# canSlaveV02_16s.net
KiCad netlist of a schematic drawn in EAGLE
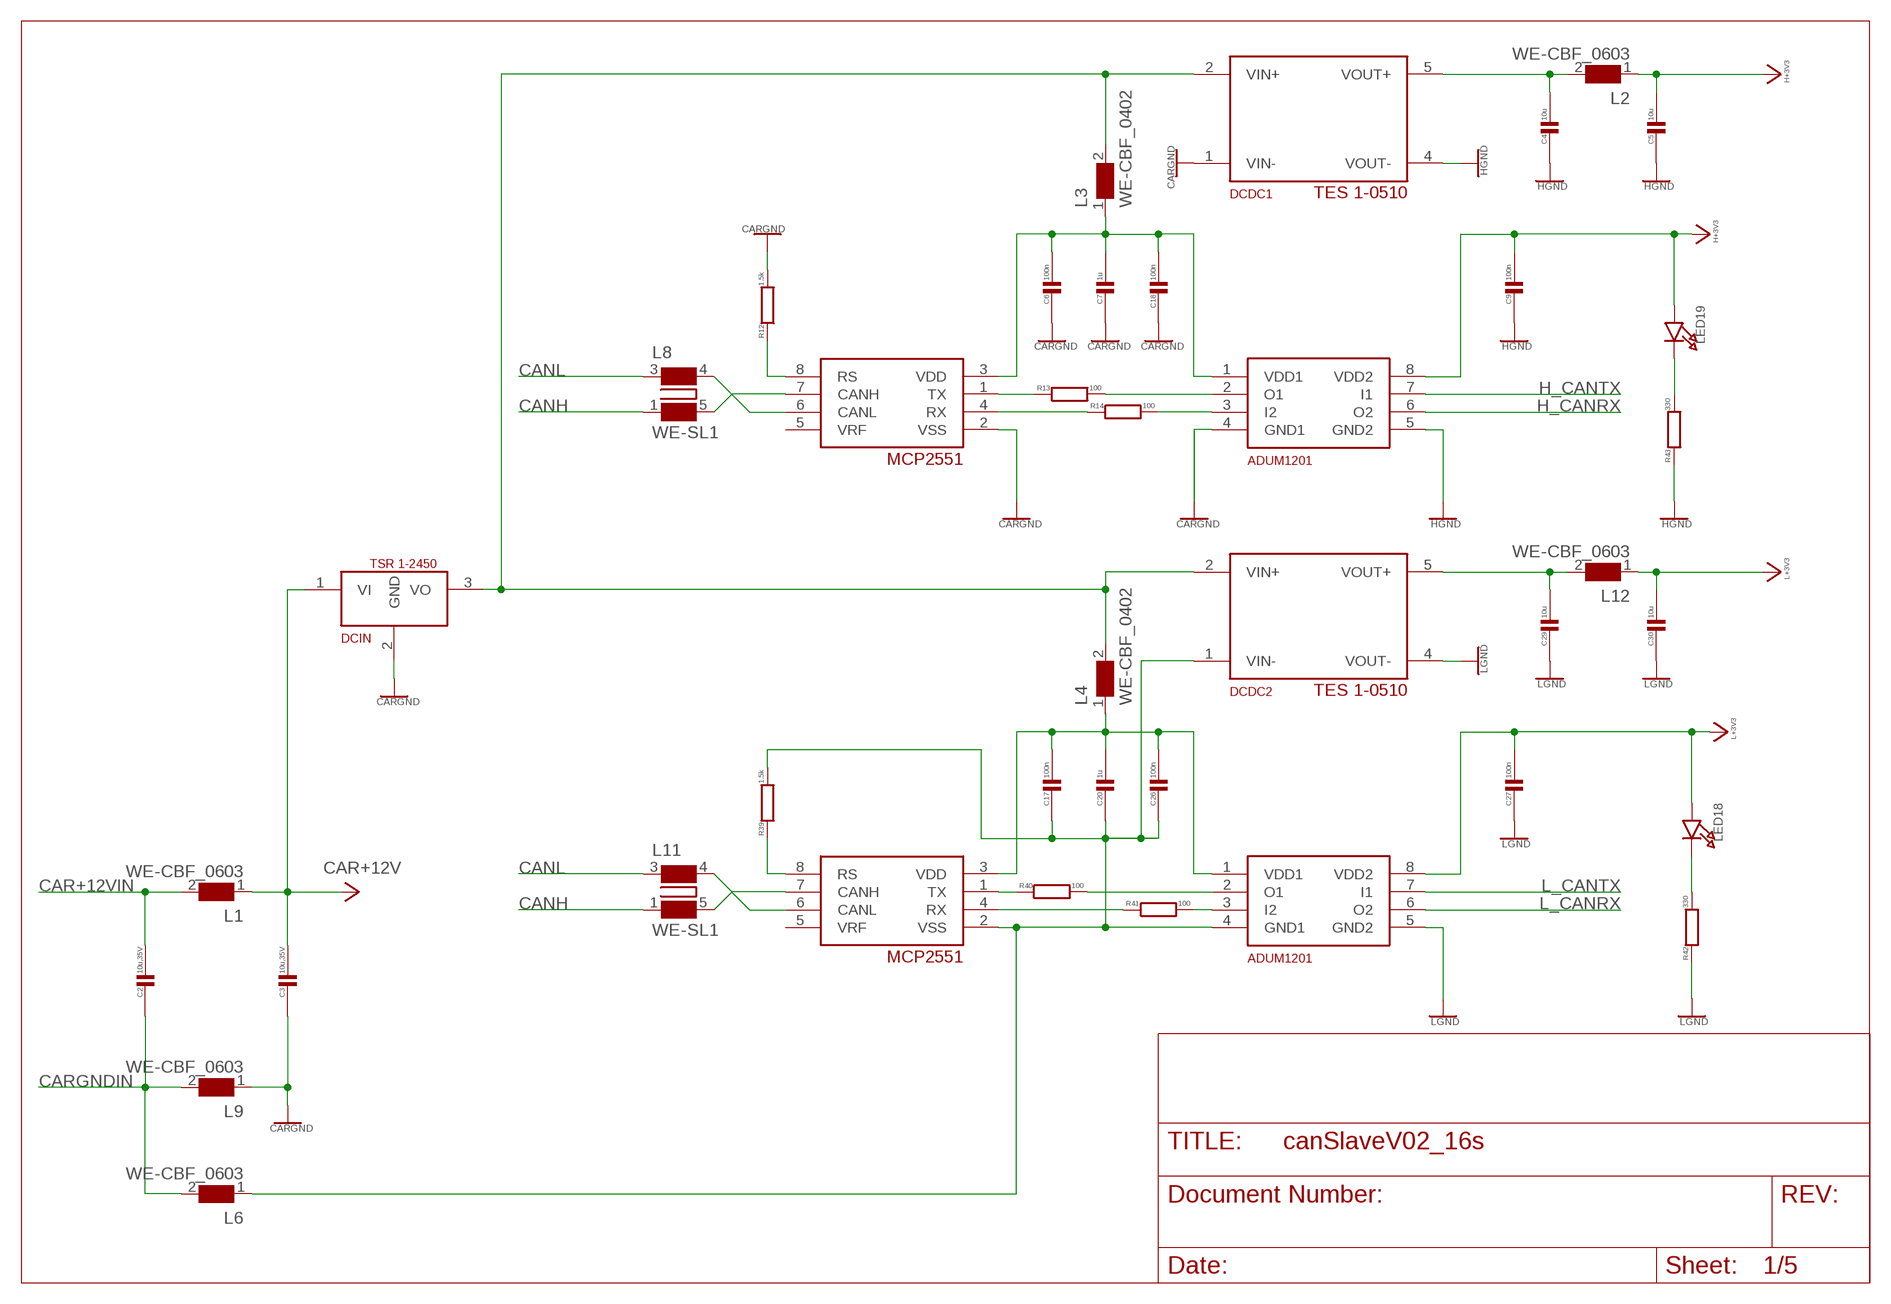
[diagram p0: schematic, sheet 1]
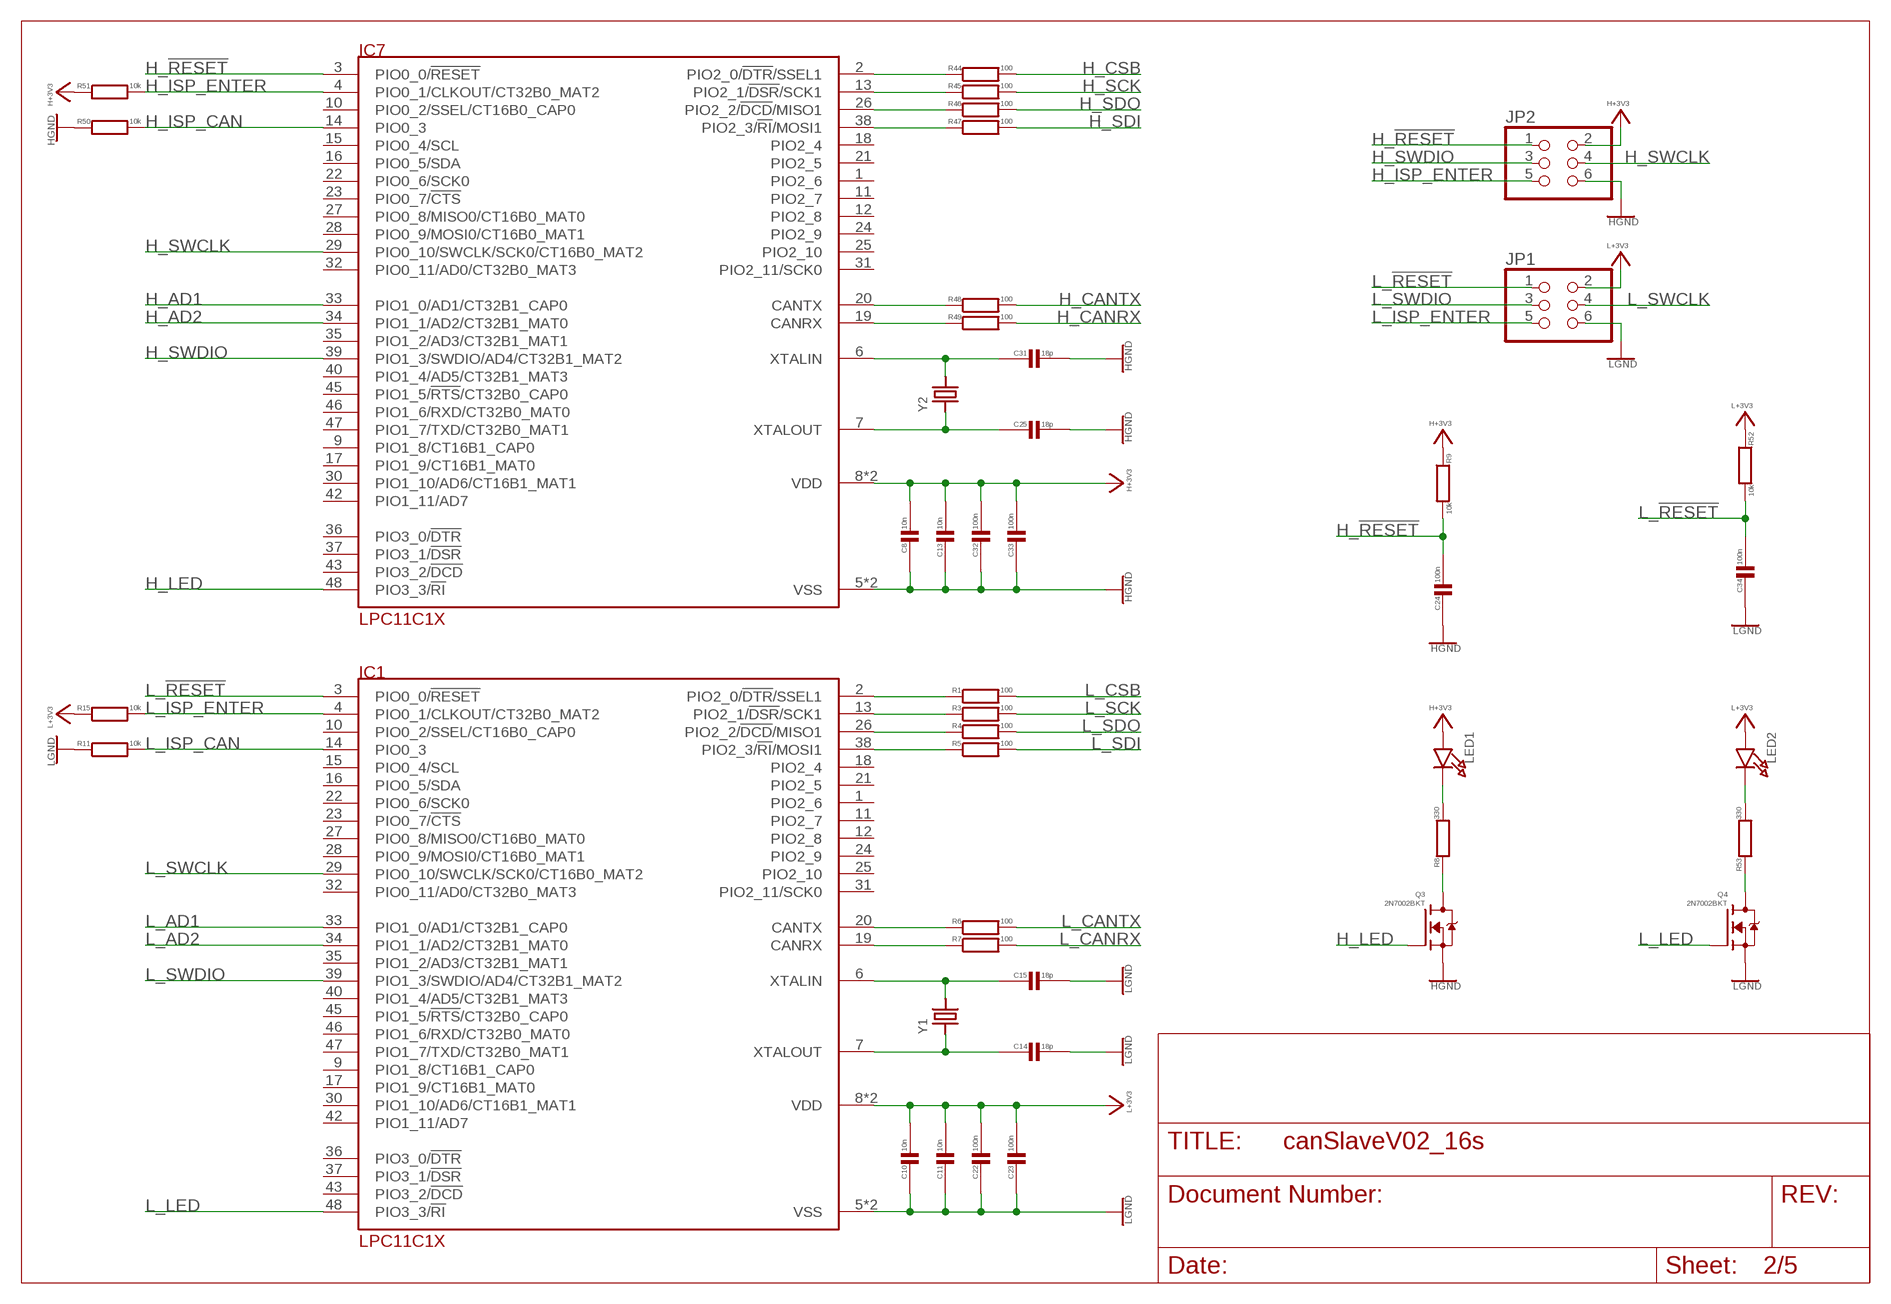
[diagram p1: schematic, sheet 2]
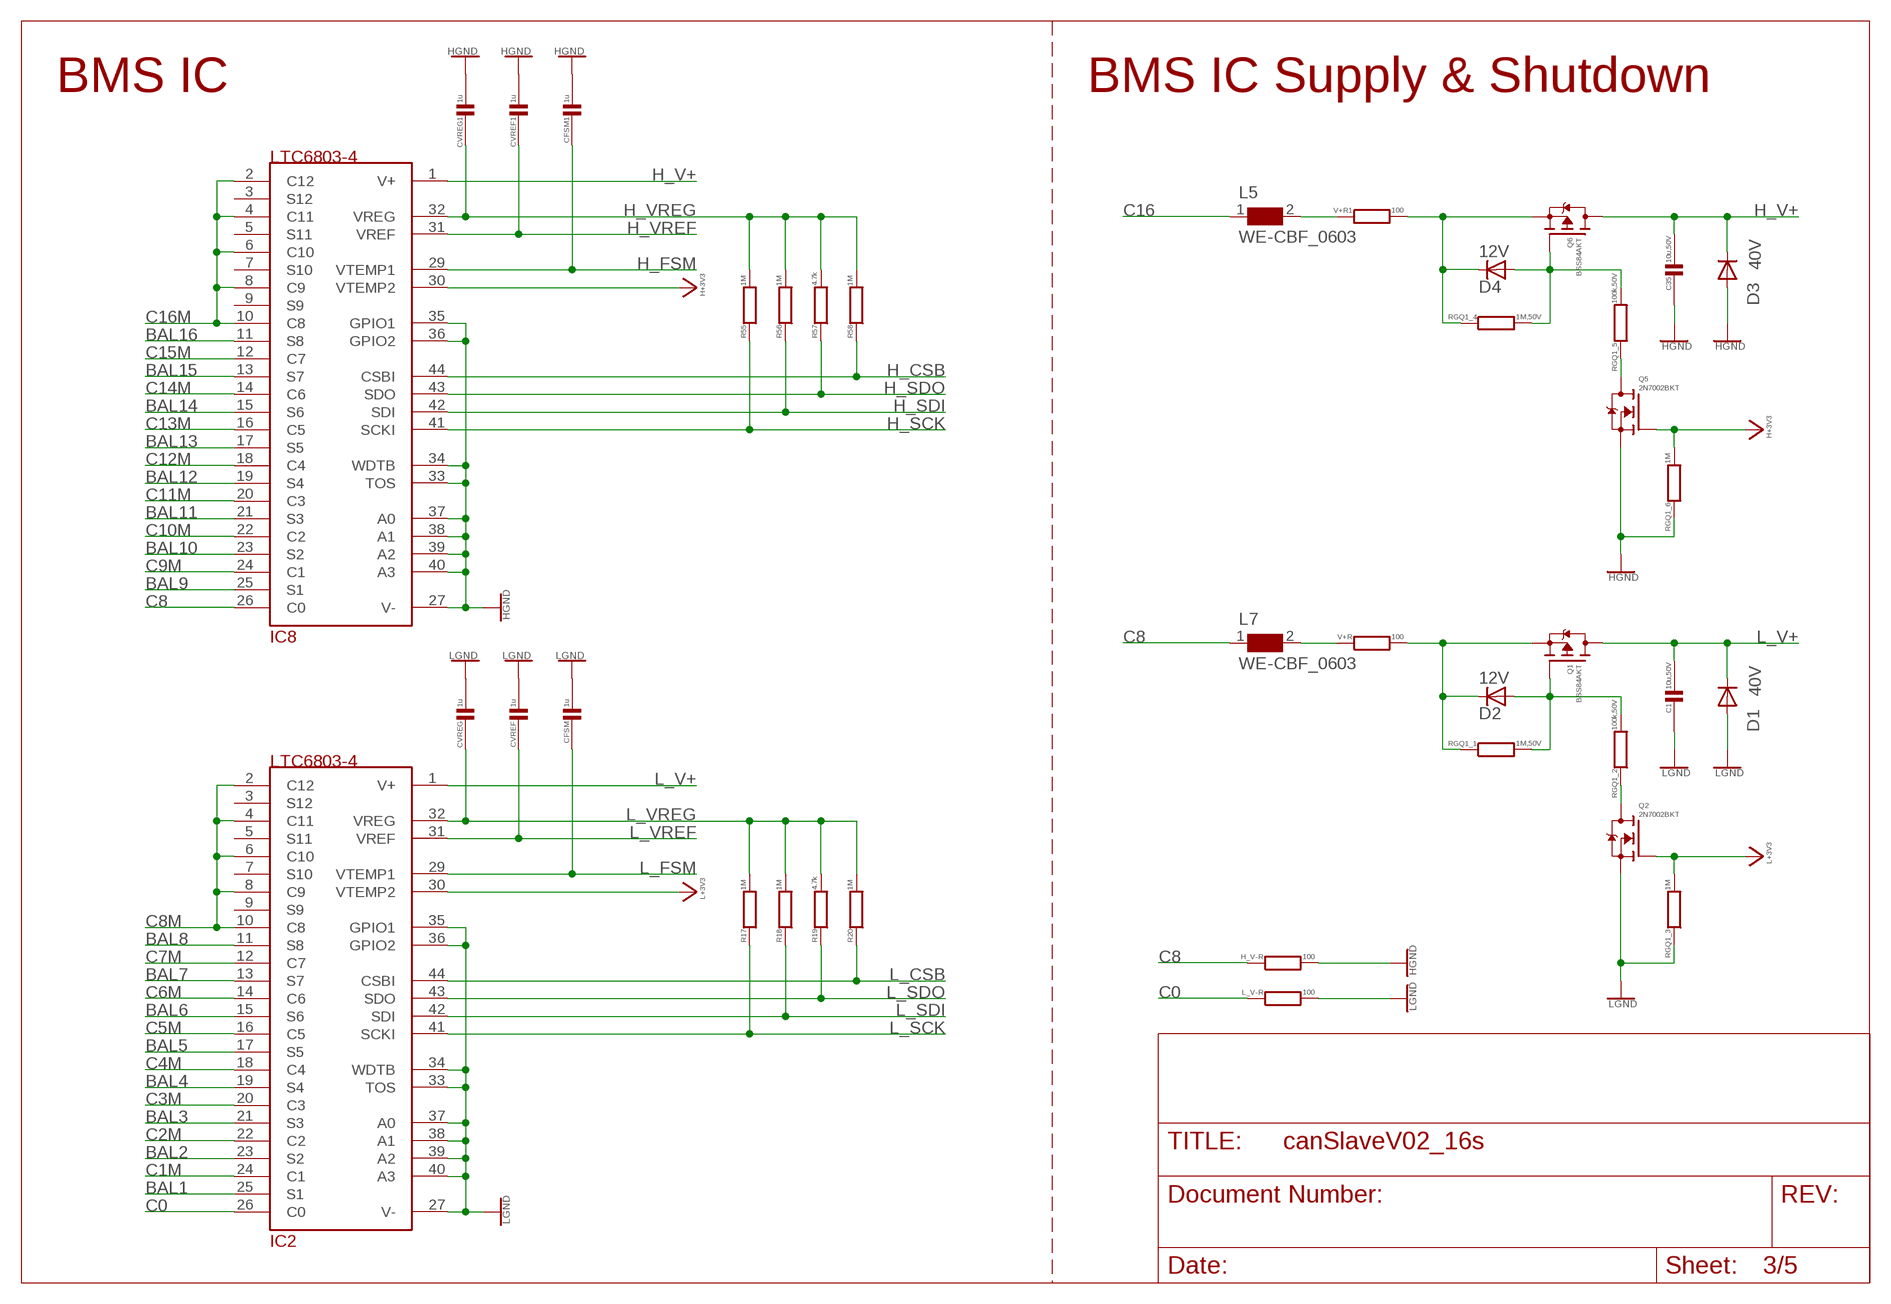
[diagram p2: schematic, sheet 3]
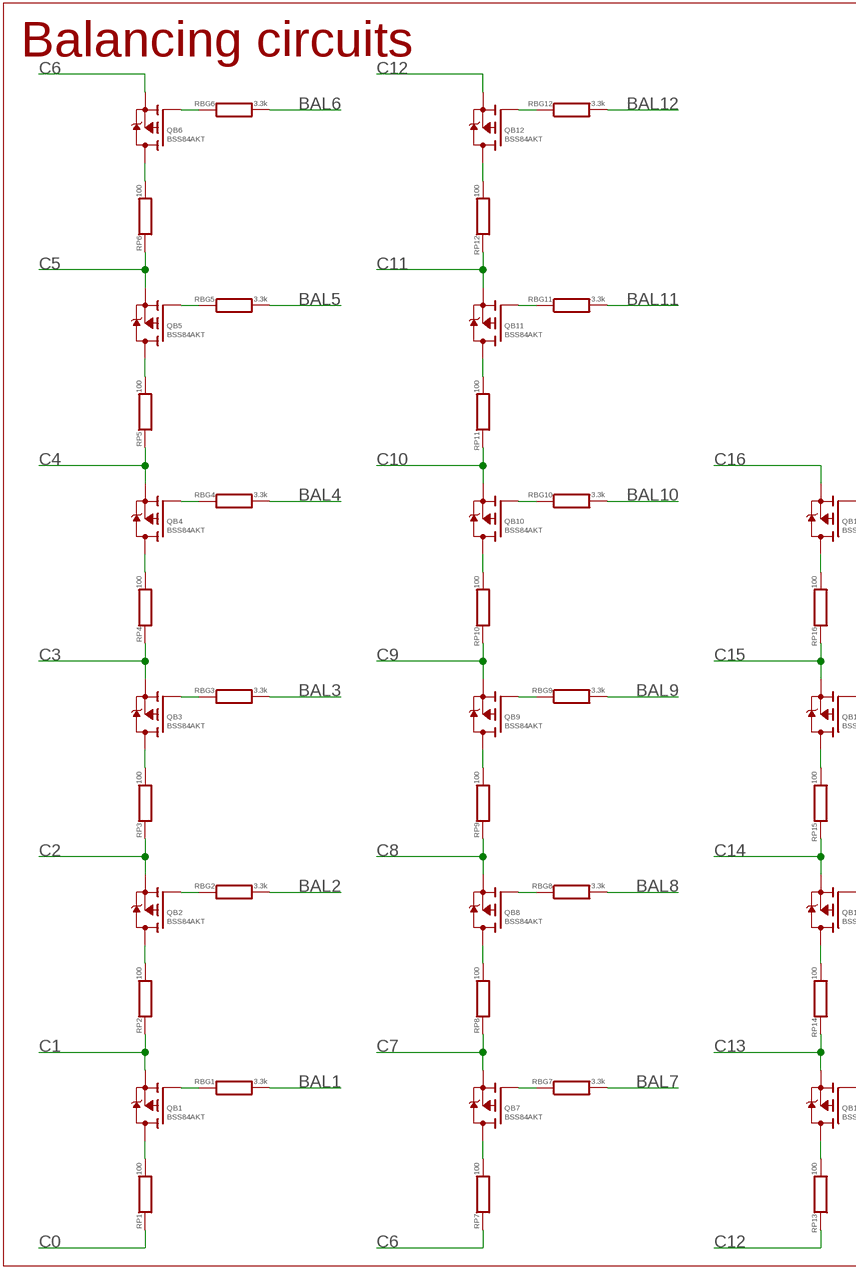
[diagram p3: schematic, sheet 4, part 1 of 2]
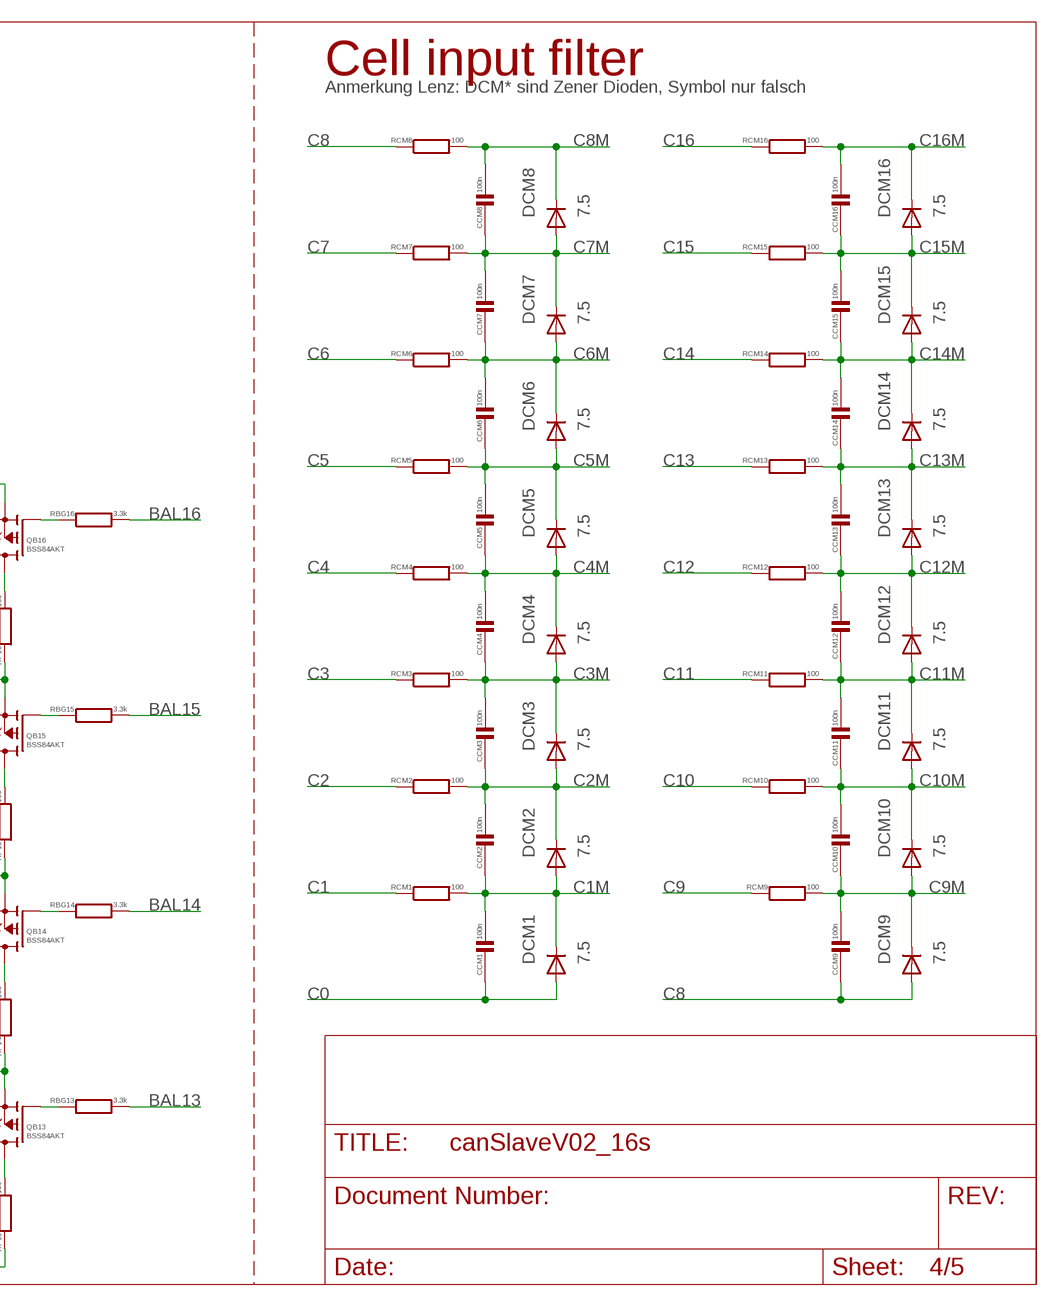
[diagram p4: schematic, sheet 4, part 2 of 2]
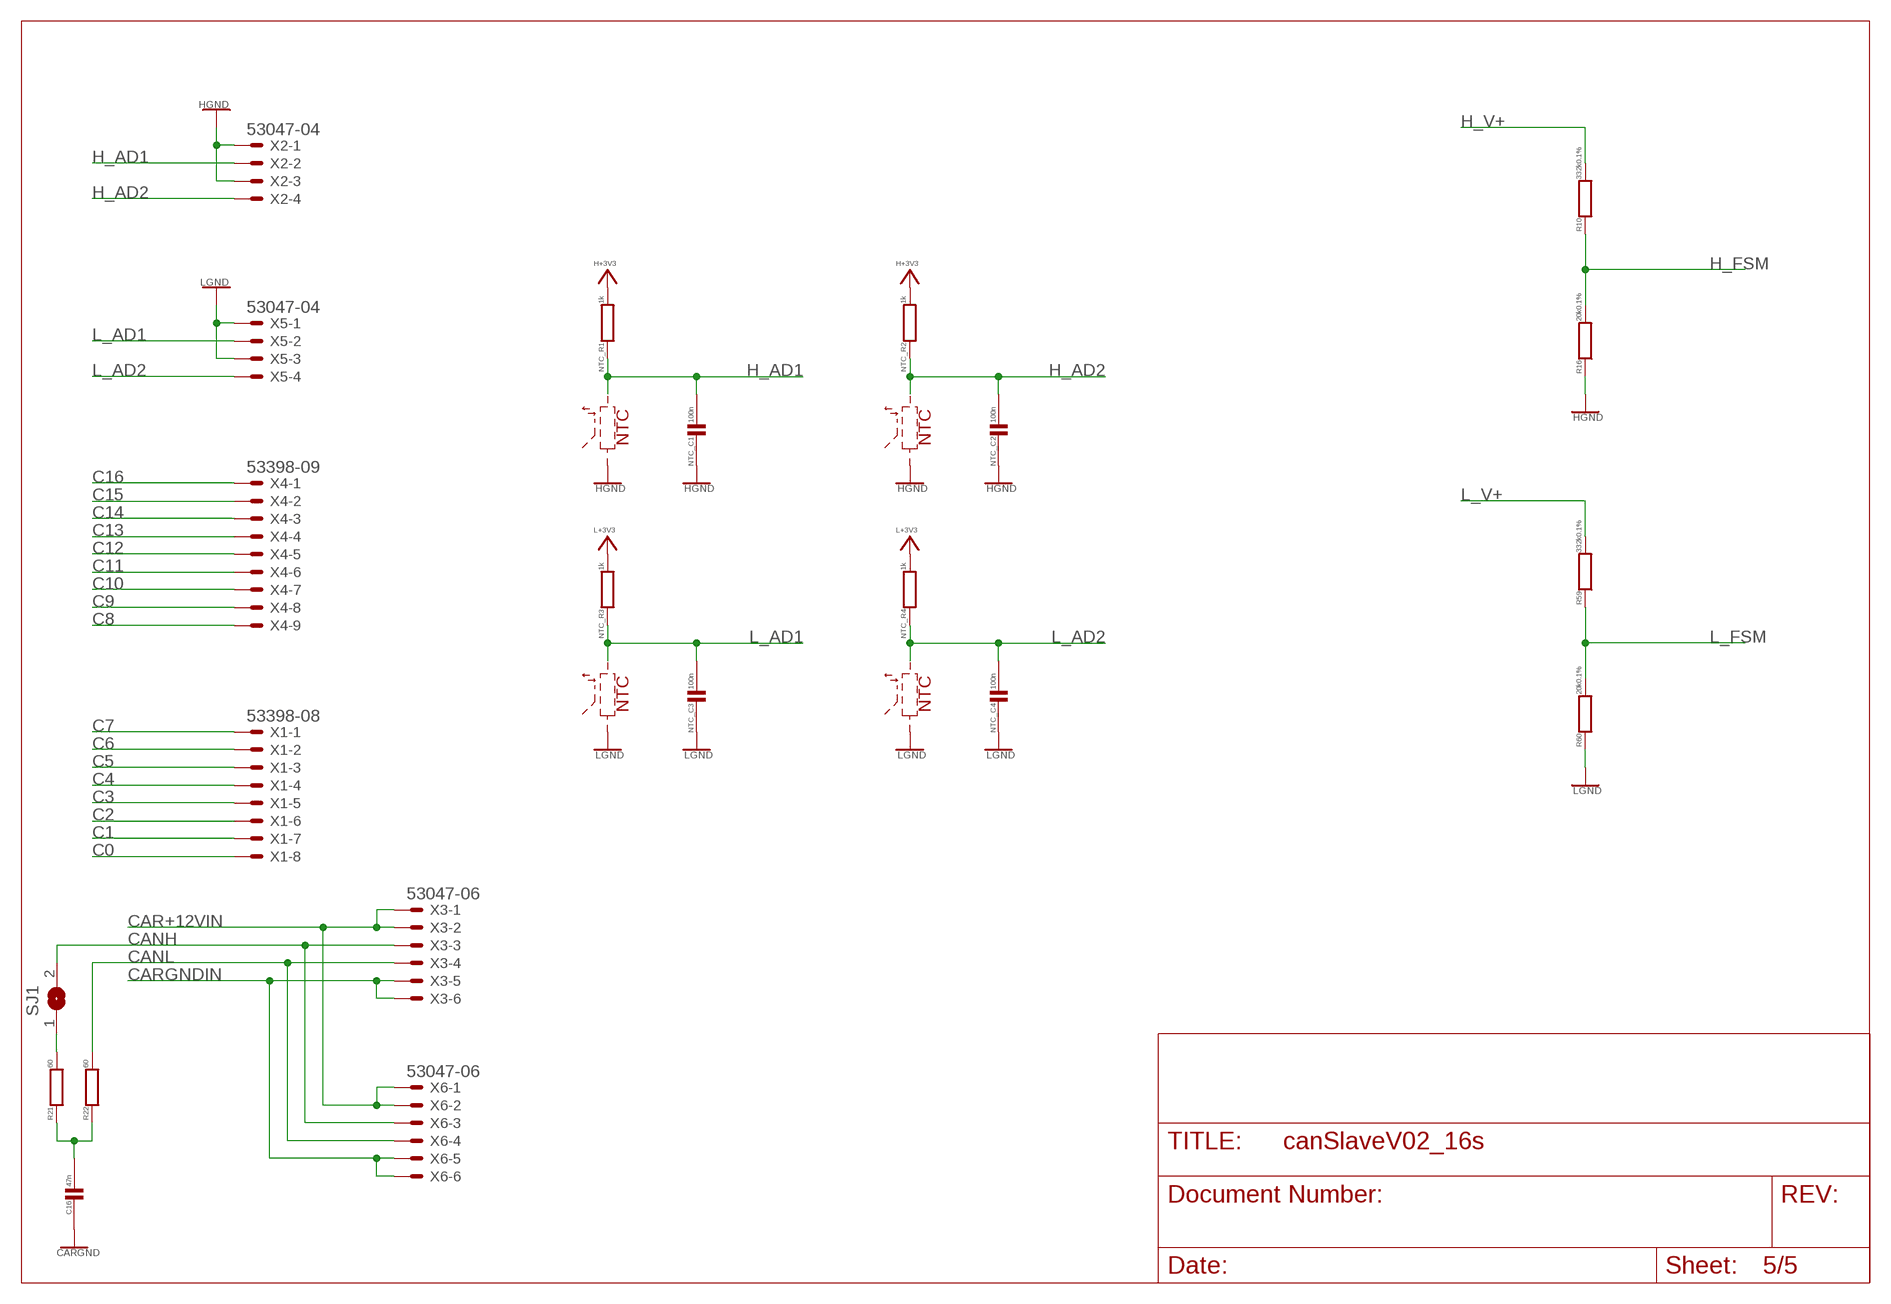
[diagram p5: schematic, sheet 5]

(export (version "E")
  (design (tool "Eeschema 10.0.6"))
  (components
    (comp (ref "C2")
      (value "10u,35V")
      (footprint "eagle-import:C0603")
      (libsource (lib "eagle-import") (part "C0603"))
    )
    (comp (ref "C3")
      (value "10u,35V")
      (footprint "eagle-import:C0603")
      (libsource (lib "eagle-import") (part "C0603"))
    )
    (comp (ref "C4")
      (value "10u")
      (footprint "eagle-import:C0603")
      (libsource (lib "eagle-import") (part "C0603"))
    )
    (comp (ref "C5")
      (value "10u")
      (footprint "eagle-import:C0603")
      (libsource (lib "eagle-import") (part "C0603"))
    )
    (comp (ref "C6")
      (value "100n")
      (footprint "eagle-import:C0402")
      (libsource (lib "eagle-import") (part "C0402"))
    )
    (comp (ref "C7")
      (value "1u")
      (footprint "eagle-import:C0402")
      (libsource (lib "eagle-import") (part "C0402"))
    )
    (comp (ref "C9")
      (value "100n")
      (footprint "eagle-import:C0402")
      (libsource (lib "eagle-import") (part "C0402"))
    )
    (comp (ref "C17")
      (value "100n")
      (footprint "eagle-import:C0402")
      (libsource (lib "eagle-import") (part "C0402"))
    )
    (comp (ref "C18")
      (value "100n")
      (footprint "eagle-import:C0402")
      (libsource (lib "eagle-import") (part "C0402"))
    )
    (comp (ref "C20")
      (value "1u")
      (footprint "eagle-import:C0402")
      (libsource (lib "eagle-import") (part "C0402"))
    )
    (comp (ref "C26")
      (value "100n")
      (footprint "eagle-import:C0402")
      (libsource (lib "eagle-import") (part "C0402"))
    )
    (comp (ref "C27")
      (value "100n")
      (footprint "eagle-import:C0402")
      (libsource (lib "eagle-import") (part "C0402"))
    )
    (comp (ref "C29")
      (value "10u")
      (footprint "eagle-import:C0603")
      (libsource (lib "eagle-import") (part "C0603"))
    )
    (comp (ref "C30")
      (value "10u")
      (footprint "eagle-import:C0603")
      (libsource (lib "eagle-import") (part "C0603"))
    )
    (comp (ref "DCDC1")
      (value "TES 1-0510")
      (footprint "eagle-import:ISF")
      (libsource (lib "eagle-import") (part "ISFXXXXA"))
    )
    (comp (ref "DCDC2")
      (value "TES 1-0510")
      (footprint "eagle-import:ISF")
      (libsource (lib "eagle-import") (part "ISFXXXXA"))
    )
    (comp (ref "DCIN")
      (value "TSR 1-2450")
      (footprint "eagle-import:TSR1")
      (libsource (lib "eagle-import") (part "TSR1"))
    )
    (comp (ref "IC3")
      (value "ADUM1201")
      (footprint "eagle-import:SO-8")
      (libsource (lib "eagle-import") (part "ADUM1201"))
    )
    (comp (ref "IC4")
      (value "MCP2551")
      (footprint "eagle-import:SO-8")
      (libsource (lib "eagle-import") (part "MCP2551"))
    )
    (comp (ref "IC5")
      (value "MCP2551")
      (footprint "eagle-import:SO-8")
      (libsource (lib "eagle-import") (part "MCP2551"))
    )
    (comp (ref "IC6")
      (value "ADUM1201")
      (footprint "eagle-import:SO-8")
      (libsource (lib "eagle-import") (part "ADUM1201"))
    )
    (comp (ref "L1")
      (value "WE-CBF_0603")
      (footprint "eagle-import:0603")
      (libsource (lib "eagle-import") (part "WE-CBF_0603"))
    )
    (comp (ref "L2")
      (value "WE-CBF_0603")
      (footprint "eagle-import:0603")
      (libsource (lib "eagle-import") (part "WE-CBF_0603"))
    )
    (comp (ref "L3")
      (value "WE-CBF_0402")
      (footprint "eagle-import:0402")
      (libsource (lib "eagle-import") (part "WE-CBF_0402"))
    )
    (comp (ref "L4")
      (value "WE-CBF_0402")
      (footprint "eagle-import:0402")
      (libsource (lib "eagle-import") (part "WE-CBF_0402"))
    )
    (comp (ref "L6")
      (value "WE-CBF_0603")
      (footprint "eagle-import:0603")
      (libsource (lib "eagle-import") (part "WE-CBF_0603"))
    )
    (comp (ref "L8")
      (value "WE-SL1")
      (footprint "eagle-import:WE-SL1")
      (libsource (lib "eagle-import") (part "WE-SL1"))
    )
    (comp (ref "L9")
      (value "WE-CBF_0603")
      (footprint "eagle-import:0603")
      (libsource (lib "eagle-import") (part "WE-CBF_0603"))
    )
    (comp (ref "L11")
      (value "WE-SL1")
      (footprint "eagle-import:WE-SL1")
      (libsource (lib "eagle-import") (part "WE-SL1"))
    )
    (comp (ref "L12")
      (value "WE-CBF_0603")
      (footprint "eagle-import:0603")
      (libsource (lib "eagle-import") (part "WE-CBF_0603"))
    )
    (comp (ref "LED18")
      (value "LED0603")
      (footprint "eagle-import:CHIPLED_0603")
      (libsource (lib "eagle-import") (part "LED0603"))
    )
    (comp (ref "LED19")
      (value "LED0603")
      (footprint "eagle-import:CHIPLED_0603")
      (libsource (lib "eagle-import") (part "LED0603"))
    )
    (comp (ref "R12")
      (value "1.5k")
      (footprint "eagle-import:R0402")
      (libsource (lib "eagle-import") (part "R0402"))
    )
    (comp (ref "R13")
      (value "100")
      (footprint "eagle-import:R0402")
      (libsource (lib "eagle-import") (part "R0402"))
    )
    (comp (ref "R14")
      (value "100")
      (footprint "eagle-import:R0402")
      (libsource (lib "eagle-import") (part "R0402"))
    )
    (comp (ref "R39")
      (value "1.5k")
      (footprint "eagle-import:R0402")
      (libsource (lib "eagle-import") (part "R0402"))
    )
    (comp (ref "R40")
      (value "100")
      (footprint "eagle-import:R0402")
      (libsource (lib "eagle-import") (part "R0402"))
    )
    (comp (ref "R41")
      (value "100")
      (footprint "eagle-import:R0402")
      (libsource (lib "eagle-import") (part "R0402"))
    )
    (comp (ref "R42")
      (value "330")
      (footprint "eagle-import:R0603")
      (libsource (lib "eagle-import") (part "R0603"))
    )
    (comp (ref "R43")
      (value "330")
      (footprint "eagle-import:R0603")
      (libsource (lib "eagle-import") (part "R0603"))
    )
    (comp (ref "CCM1")
      (value "100n")
      (footprint "eagle-import:C0402")
      (libsource (lib "eagle-import") (part "C0402"))
    )
    (comp (ref "CCM2")
      (value "100n")
      (footprint "eagle-import:C0402")
      (libsource (lib "eagle-import") (part "C0402"))
    )
    (comp (ref "CCM3")
      (value "100n")
      (footprint "eagle-import:C0402")
      (libsource (lib "eagle-import") (part "C0402"))
    )
    (comp (ref "CCM4")
      (value "100n")
      (footprint "eagle-import:C0402")
      (libsource (lib "eagle-import") (part "C0402"))
    )
    (comp (ref "CCM5")
      (value "100n")
      (footprint "eagle-import:C0402")
      (libsource (lib "eagle-import") (part "C0402"))
    )
    (comp (ref "CCM6")
      (value "100n")
      (footprint "eagle-import:C0402")
      (libsource (lib "eagle-import") (part "C0402"))
    )
    (comp (ref "CCM7")
      (value "100n")
      (footprint "eagle-import:C0402")
      (libsource (lib "eagle-import") (part "C0402"))
    )
    (comp (ref "CCM8")
      (value "100n")
      (footprint "eagle-import:C0402")
      (libsource (lib "eagle-import") (part "C0402"))
    )
    (comp (ref "CCM9")
      (value "100n")
      (footprint "eagle-import:C0402")
      (libsource (lib "eagle-import") (part "C0402"))
    )
    (comp (ref "CCM10")
      (value "100n")
      (footprint "eagle-import:C0402")
      (libsource (lib "eagle-import") (part "C0402"))
    )
    (comp (ref "CCM11")
      (value "100n")
      (footprint "eagle-import:C0402")
      (libsource (lib "eagle-import") (part "C0402"))
    )
    (comp (ref "CCM12")
      (value "100n")
      (footprint "eagle-import:C0402")
      (libsource (lib "eagle-import") (part "C0402"))
    )
    (comp (ref "CCM13")
      (value "100n")
      (footprint "eagle-import:C0402")
      (libsource (lib "eagle-import") (part "C0402"))
    )
    (comp (ref "CCM14")
      (value "100n")
      (footprint "eagle-import:C0402")
      (libsource (lib "eagle-import") (part "C0402"))
    )
    (comp (ref "CCM15")
      (value "100n")
      (footprint "eagle-import:C0402")
      (libsource (lib "eagle-import") (part "C0402"))
    )
    (comp (ref "CCM16")
      (value "100n")
      (footprint "eagle-import:C0402")
      (libsource (lib "eagle-import") (part "C0402"))
    )
    (comp (ref "DCM1")
      (value "7.5")
      (footprint "eagle-import:SOD323-R")
      (libsource (lib "eagle-import") (part "DIODE-SOD323-R"))
    )
    (comp (ref "DCM2")
      (value "7.5")
      (footprint "eagle-import:SOD323-R")
      (libsource (lib "eagle-import") (part "DIODE-SOD323-R"))
    )
    (comp (ref "DCM3")
      (value "7.5")
      (footprint "eagle-import:SOD323-R")
      (libsource (lib "eagle-import") (part "DIODE-SOD323-R"))
    )
    (comp (ref "DCM4")
      (value "7.5")
      (footprint "eagle-import:SOD323-R")
      (libsource (lib "eagle-import") (part "DIODE-SOD323-R"))
    )
    (comp (ref "DCM5")
      (value "7.5")
      (footprint "eagle-import:SOD323-R")
      (libsource (lib "eagle-import") (part "DIODE-SOD323-R"))
    )
    (comp (ref "DCM6")
      (value "7.5")
      (footprint "eagle-import:SOD323-R")
      (libsource (lib "eagle-import") (part "DIODE-SOD323-R"))
    )
    (comp (ref "DCM7")
      (value "7.5")
      (footprint "eagle-import:SOD323-R")
      (libsource (lib "eagle-import") (part "DIODE-SOD323-R"))
    )
    (comp (ref "DCM8")
      (value "7.5")
      (footprint "eagle-import:SOD323-R")
      (libsource (lib "eagle-import") (part "DIODE-SOD323-R"))
    )
    (comp (ref "DCM9")
      (value "7.5")
      (footprint "eagle-import:SOD323-R")
      (libsource (lib "eagle-import") (part "DIODE-SOD323-R"))
    )
    (comp (ref "DCM10")
      (value "7.5")
      (footprint "eagle-import:SOD323-R")
      (libsource (lib "eagle-import") (part "DIODE-SOD323-R"))
    )
    (comp (ref "DCM11")
      (value "7.5")
      (footprint "eagle-import:SOD323-R")
      (libsource (lib "eagle-import") (part "DIODE-SOD323-R"))
    )
    (comp (ref "DCM12")
      (value "7.5")
      (footprint "eagle-import:SOD323-R")
      (libsource (lib "eagle-import") (part "DIODE-SOD323-R"))
    )
    (comp (ref "DCM13")
      (value "7.5")
      (footprint "eagle-import:SOD323-R")
      (libsource (lib "eagle-import") (part "DIODE-SOD323-R"))
    )
    (comp (ref "DCM14")
      (value "7.5")
      (footprint "eagle-import:SOD323-R")
      (libsource (lib "eagle-import") (part "DIODE-SOD323-R"))
    )
    (comp (ref "DCM15")
      (value "7.5")
      (footprint "eagle-import:SOD323-R")
      (libsource (lib "eagle-import") (part "DIODE-SOD323-R"))
    )
    (comp (ref "DCM16")
      (value "7.5")
      (footprint "eagle-import:SOD323-R")
      (libsource (lib "eagle-import") (part "DIODE-SOD323-R"))
    )
    (comp (ref "QB1")
      (value "BSS84AKT")
      (footprint "eagle-import:SOT416")
      (libsource (lib "eagle-import") (part "BSS84AKT"))
    )
    (comp (ref "QB2")
      (value "BSS84AKT")
      (footprint "eagle-import:SOT416")
      (libsource (lib "eagle-import") (part "BSS84AKT"))
    )
    (comp (ref "QB3")
      (value "BSS84AKT")
      (footprint "eagle-import:SOT416")
      (libsource (lib "eagle-import") (part "BSS84AKT"))
    )
    (comp (ref "QB4")
      (value "BSS84AKT")
      (footprint "eagle-import:SOT416")
      (libsource (lib "eagle-import") (part "BSS84AKT"))
    )
    (comp (ref "QB5")
      (value "BSS84AKT")
      (footprint "eagle-import:SOT416")
      (libsource (lib "eagle-import") (part "BSS84AKT"))
    )
    (comp (ref "QB6")
      (value "BSS84AKT")
      (footprint "eagle-import:SOT416")
      (libsource (lib "eagle-import") (part "BSS84AKT"))
    )
    (comp (ref "QB7")
      (value "BSS84AKT")
      (footprint "eagle-import:SOT416")
      (libsource (lib "eagle-import") (part "BSS84AKT"))
    )
    (comp (ref "QB8")
      (value "BSS84AKT")
      (footprint "eagle-import:SOT416")
      (libsource (lib "eagle-import") (part "BSS84AKT"))
    )
    (comp (ref "QB9")
      (value "BSS84AKT")
      (footprint "eagle-import:SOT416")
      (libsource (lib "eagle-import") (part "BSS84AKT"))
    )
    (comp (ref "QB10")
      (value "BSS84AKT")
      (footprint "eagle-import:SOT416")
      (libsource (lib "eagle-import") (part "BSS84AKT"))
    )
    (comp (ref "QB11")
      (value "BSS84AKT")
      (footprint "eagle-import:SOT416")
      (libsource (lib "eagle-import") (part "BSS84AKT"))
    )
    (comp (ref "QB12")
      (value "BSS84AKT")
      (footprint "eagle-import:SOT416")
      (libsource (lib "eagle-import") (part "BSS84AKT"))
    )
    (comp (ref "QB13")
      (value "BSS84AKT")
      (footprint "eagle-import:SOT416")
      (libsource (lib "eagle-import") (part "BSS84AKT"))
    )
    (comp (ref "QB14")
      (value "BSS84AKT")
      (footprint "eagle-import:SOT416")
      (libsource (lib "eagle-import") (part "BSS84AKT"))
    )
    (comp (ref "QB15")
      (value "BSS84AKT")
      (footprint "eagle-import:SOT416")
      (libsource (lib "eagle-import") (part "BSS84AKT"))
    )
    (comp (ref "QB16")
      (value "BSS84AKT")
      (footprint "eagle-import:SOT416")
      (libsource (lib "eagle-import") (part "BSS84AKT"))
    )
    (comp (ref "RBG1")
      (value "3.3k")
      (footprint "eagle-import:R0402")
      (libsource (lib "eagle-import") (part "R0402"))
    )
    (comp (ref "RBG2")
      (value "3.3k")
      (footprint "eagle-import:R0402")
      (libsource (lib "eagle-import") (part "R0402"))
    )
    (comp (ref "RBG3")
      (value "3.3k")
      (footprint "eagle-import:R0402")
      (libsource (lib "eagle-import") (part "R0402"))
    )
    (comp (ref "RBG4")
      (value "3.3k")
      (footprint "eagle-import:R0402")
      (libsource (lib "eagle-import") (part "R0402"))
    )
    (comp (ref "RBG5")
      (value "3.3k")
      (footprint "eagle-import:R0402")
      (libsource (lib "eagle-import") (part "R0402"))
    )
    (comp (ref "RBG6")
      (value "3.3k")
      (footprint "eagle-import:R0402")
      (libsource (lib "eagle-import") (part "R0402"))
    )
    (comp (ref "RBG7")
      (value "3.3k")
      (footprint "eagle-import:R0402")
      (libsource (lib "eagle-import") (part "R0402"))
    )
    (comp (ref "RBG8")
      (value "3.3k")
      (footprint "eagle-import:R0402")
      (libsource (lib "eagle-import") (part "R0402"))
    )
    (comp (ref "RBG9")
      (value "3.3k")
      (footprint "eagle-import:R0402")
      (libsource (lib "eagle-import") (part "R0402"))
    )
    (comp (ref "RBG10")
      (value "3.3k")
      (footprint "eagle-import:R0402")
      (libsource (lib "eagle-import") (part "R0402"))
    )
    (comp (ref "RBG11")
      (value "3.3k")
      (footprint "eagle-import:R0402")
      (libsource (lib "eagle-import") (part "R0402"))
    )
    (comp (ref "RBG12")
      (value "3.3k")
      (footprint "eagle-import:R0402")
      (libsource (lib "eagle-import") (part "R0402"))
    )
    (comp (ref "RBG13")
      (value "3.3k")
      (footprint "eagle-import:R0402")
      (libsource (lib "eagle-import") (part "R0402"))
    )
    (comp (ref "RBG14")
      (value "3.3k")
      (footprint "eagle-import:R0402")
      (libsource (lib "eagle-import") (part "R0402"))
    )
    (comp (ref "RBG15")
      (value "3.3k")
      (footprint "eagle-import:R0402")
      (libsource (lib "eagle-import") (part "R0402"))
    )
    (comp (ref "RBG16")
      (value "3.3k")
      (footprint "eagle-import:R0402")
      (libsource (lib "eagle-import") (part "R0402"))
    )
    (comp (ref "RCM1")
      (value "100")
      (footprint "eagle-import:R0402")
      (libsource (lib "eagle-import") (part "R0402"))
    )
    (comp (ref "RCM2")
      (value "100")
      (footprint "eagle-import:R0402")
      (libsource (lib "eagle-import") (part "R0402"))
    )
    (comp (ref "RCM3")
      (value "100")
      (footprint "eagle-import:R0402")
      (libsource (lib "eagle-import") (part "R0402"))
    )
    (comp (ref "RCM4")
      (value "100")
      (footprint "eagle-import:R0402")
      (libsource (lib "eagle-import") (part "R0402"))
    )
    (comp (ref "RCM5")
      (value "100")
      (footprint "eagle-import:R0402")
      (libsource (lib "eagle-import") (part "R0402"))
    )
    (comp (ref "RCM6")
      (value "100")
      (footprint "eagle-import:R0402")
      (libsource (lib "eagle-import") (part "R0402"))
    )
    (comp (ref "RCM7")
      (value "100")
      (footprint "eagle-import:R0402")
      (libsource (lib "eagle-import") (part "R0402"))
    )
    (comp (ref "RCM8")
      (value "100")
      (footprint "eagle-import:R0402")
      (libsource (lib "eagle-import") (part "R0402"))
    )
    (comp (ref "RCM9")
      (value "100")
      (footprint "eagle-import:R0402")
      (libsource (lib "eagle-import") (part "R0402"))
    )
    (comp (ref "RCM10")
      (value "100")
      (footprint "eagle-import:R0402")
      (libsource (lib "eagle-import") (part "R0402"))
    )
    (comp (ref "RCM11")
      (value "100")
      (footprint "eagle-import:R0402")
      (libsource (lib "eagle-import") (part "R0402"))
    )
    (comp (ref "RCM12")
      (value "100")
      (footprint "eagle-import:R0402")
      (libsource (lib "eagle-import") (part "R0402"))
    )
    (comp (ref "RCM13")
      (value "100")
      (footprint "eagle-import:R0402")
      (libsource (lib "eagle-import") (part "R0402"))
    )
    (comp (ref "RCM14")
      (value "100")
      (footprint "eagle-import:R0402")
      (libsource (lib "eagle-import") (part "R0402"))
    )
    (comp (ref "RCM15")
      (value "100")
      (footprint "eagle-import:R0402")
      (libsource (lib "eagle-import") (part "R0402"))
    )
    (comp (ref "RCM16")
      (value "100")
      (footprint "eagle-import:R0402")
      (libsource (lib "eagle-import") (part "R0402"))
    )
    (comp (ref "RP1")
      (value "100")
      (footprint "eagle-import:R2512")
      (libsource (lib "eagle-import") (part "R2512"))
    )
    (comp (ref "RP2")
      (value "100")
      (footprint "eagle-import:R2512")
      (libsource (lib "eagle-import") (part "R2512"))
    )
    (comp (ref "RP3")
      (value "100")
      (footprint "eagle-import:R2512")
      (libsource (lib "eagle-import") (part "R2512"))
    )
    (comp (ref "RP4")
      (value "100")
      (footprint "eagle-import:R2512")
      (libsource (lib "eagle-import") (part "R2512"))
    )
    (comp (ref "RP5")
      (value "100")
      (footprint "eagle-import:R2512")
      (libsource (lib "eagle-import") (part "R2512"))
    )
    (comp (ref "RP6")
      (value "100")
      (footprint "eagle-import:R2512")
      (libsource (lib "eagle-import") (part "R2512"))
    )
    (comp (ref "RP7")
      (value "100")
      (footprint "eagle-import:R2512")
      (libsource (lib "eagle-import") (part "R2512"))
    )
    (comp (ref "RP8")
      (value "100")
      (footprint "eagle-import:R2512")
      (libsource (lib "eagle-import") (part "R2512"))
    )
    (comp (ref "RP9")
      (value "100")
      (footprint "eagle-import:R2512")
      (libsource (lib "eagle-import") (part "R2512"))
    )
    (comp (ref "RP10")
      (value "100")
      (footprint "eagle-import:R2512")
      (libsource (lib "eagle-import") (part "R2512"))
    )
    (comp (ref "RP11")
      (value "100")
      (footprint "eagle-import:R2512")
      (libsource (lib "eagle-import") (part "R2512"))
    )
    (comp (ref "RP12")
      (value "100")
      (footprint "eagle-import:R2512")
      (libsource (lib "eagle-import") (part "R2512"))
    )
    (comp (ref "RP13")
      (value "100")
      (footprint "eagle-import:R2512")
      (libsource (lib "eagle-import") (part "R2512"))
    )
    (comp (ref "RP14")
      (value "100")
      (footprint "eagle-import:R2512")
      (libsource (lib "eagle-import") (part "R2512"))
    )
    (comp (ref "RP15")
      (value "100")
      (footprint "eagle-import:R2512")
      (libsource (lib "eagle-import") (part "R2512"))
    )
    (comp (ref "RP16")
      (value "100")
      (footprint "eagle-import:R2512")
      (libsource (lib "eagle-import") (part "R2512"))
    )
    (comp (ref "C16")
      (value "47n")
      (footprint "eagle-import:C0402")
      (libsource (lib "eagle-import") (part "C0402"))
    )
    (comp (ref "NTC_C1")
      (value "100n")
      (footprint "eagle-import:C0402")
      (libsource (lib "eagle-import") (part "C0402"))
    )
    (comp (ref "NTC_C2")
      (value "100n")
      (footprint "eagle-import:C0402")
      (libsource (lib "eagle-import") (part "C0402"))
    )
    (comp (ref "NTC_C3")
      (value "100n")
      (footprint "eagle-import:C0402")
      (libsource (lib "eagle-import") (part "C0402"))
    )
    (comp (ref "NTC_C4")
      (value "100n")
      (footprint "eagle-import:C0402")
      (libsource (lib "eagle-import") (part "C0402"))
    )
    (comp (ref "NTC_R1")
      (value "1k")
      (footprint "eagle-import:R0402")
      (libsource (lib "eagle-import") (part "R0402"))
    )
    (comp (ref "NTC_R2")
      (value "1k")
      (footprint "eagle-import:R0402")
      (libsource (lib "eagle-import") (part "R0402"))
    )
    (comp (ref "NTC_R3")
      (value "1k")
      (footprint "eagle-import:R0402")
      (libsource (lib "eagle-import") (part "R0402"))
    )
    (comp (ref "NTC_R4")
      (value "1k")
      (footprint "eagle-import:R0402")
      (libsource (lib "eagle-import") (part "R0402"))
    )
    (comp (ref "R10")
      (value "332k0.1%")
      (footprint "eagle-import:R0603")
      (libsource (lib "eagle-import") (part "R0603"))
    )
    (comp (ref "R16")
      (value "20k0.1%")
      (footprint "eagle-import:R0603")
      (libsource (lib "eagle-import") (part "R0603"))
    )
    (comp (ref "R21")
      (value "60")
      (footprint "eagle-import:R0402")
      (libsource (lib "eagle-import") (part "R0402"))
    )
    (comp (ref "R22")
      (value "60")
      (footprint "eagle-import:R0402")
      (libsource (lib "eagle-import") (part "R0402"))
    )
    (comp (ref "R59")
      (value "332k0.1%")
      (footprint "eagle-import:R0603")
      (libsource (lib "eagle-import") (part "R0603"))
    )
    (comp (ref "R60")
      (value "20k0.1%")
      (footprint "eagle-import:R0603")
      (libsource (lib "eagle-import") (part "R0603"))
    )
    (comp (ref "SJ1")
      (value "SOLDERJUMPERSMALL")
      (footprint "eagle-import:SOLDERJUMPER_REFLOW_NOPASTE_SMALL")
      (libsource (lib "eagle-import") (part "SOLDERJUMPERSMALL"))
    )
    (comp (ref "X1")
      (value "53398-08")
      (footprint "eagle-import:53398-08")
      (libsource (lib "eagle-import") (part "53?-08398"))
    )
    (comp (ref "X2")
      (value "53047-04")
      (footprint "eagle-import:53047-04")
      (fields
        (field (name "MF") "WALDOM/MOLEX")
        (field (name "MPN") "53047-0410")
        (field (name "MF_1") "WALDOM/MOLEX")
        (field (name "MPN_1") "53047-0410")
        (field (name "OC_FARNELL") "9733060")
        (field (name "OC_NEWARK") "38C9900")
      )
      (libsource (lib "eagle-import") (part "53?-04047"))
    )
    (comp (ref "X3")
      (value "53047-06")
      (footprint "eagle-import:53047-06")
      (fields (field (name "MPN") "53047-0610-C"))
      (libsource (lib "eagle-import") (part "53?-06047"))
    )
    (comp (ref "X4")
      (value "53398-09")
      (footprint "eagle-import:53398-09")
      (libsource (lib "eagle-import") (part "53?-09398"))
    )
    (comp (ref "X5")
      (value "53047-04")
      (footprint "eagle-import:53047-04")
      (fields
        (field (name "MF") "WALDOM/MOLEX")
        (field (name "MPN") "53047-0410")
        (field (name "MF_1") "WALDOM/MOLEX")
        (field (name "MPN_1") "53047-0410")
        (field (name "OC_FARNELL") "9733060")
        (field (name "OC_NEWARK") "38C9900")
      )
      (libsource (lib "eagle-import") (part "53?-04047"))
    )
    (comp (ref "X6")
      (value "53047-06")
      (footprint "eagle-import:53047-06")
      (fields (field (name "MPN") "53047-0610-C"))
      (libsource (lib "eagle-import") (part "53?-06047"))
    )
    (comp (ref "C1")
      (value "10u,50V")
      (footprint "eagle-import:C1206")
      (libsource (lib "eagle-import") (part "C1206"))
    )
    (comp (ref "C35")
      (value "10u,50V")
      (footprint "eagle-import:C1206")
      (libsource (lib "eagle-import") (part "C1206"))
    )
    (comp (ref "CFSM")
      (value "1u")
      (footprint "eagle-import:C0402")
      (libsource (lib "eagle-import") (part "C0402"))
    )
    (comp (ref "CFSM1")
      (value "1u")
      (footprint "eagle-import:C0402")
      (libsource (lib "eagle-import") (part "C0402"))
    )
    (comp (ref "CVREF")
      (value "1u")
      (footprint "eagle-import:C0402")
      (libsource (lib "eagle-import") (part "C0402"))
    )
    (comp (ref "CVREF1")
      (value "1u")
      (footprint "eagle-import:C0402")
      (libsource (lib "eagle-import") (part "C0402"))
    )
    (comp (ref "CVREG")
      (value "1u")
      (footprint "eagle-import:C0402")
      (libsource (lib "eagle-import") (part "C0402"))
    )
    (comp (ref "CVREG1")
      (value "1u")
      (footprint "eagle-import:C0402")
      (libsource (lib "eagle-import") (part "C0402"))
    )
    (comp (ref "D1")
      (value "40V")
      (footprint "eagle-import:SOD323-R")
      (libsource (lib "eagle-import") (part "DIODE-SOD323-R"))
    )
    (comp (ref "D2")
      (value "12V")
      (footprint "eagle-import:SOD323-R")
      (libsource (lib "eagle-import") (part "DIODE-SOD323-R"))
    )
    (comp (ref "D3")
      (value "40V")
      (footprint "eagle-import:SOD323-R")
      (libsource (lib "eagle-import") (part "DIODE-SOD323-R"))
    )
    (comp (ref "D4")
      (value "12V")
      (footprint "eagle-import:SOD323-R")
      (libsource (lib "eagle-import") (part "DIODE-SOD323-R"))
    )
    (comp (ref "H_V-R")
      (value "100")
      (footprint "eagle-import:R0402")
      (libsource (lib "eagle-import") (part "R0402"))
    )
    (comp (ref "IC2")
      (value "LTC6803-4")
      (footprint "eagle-import:44SSOP")
      (libsource (lib "eagle-import") (part "LTC6803-4"))
    )
    (comp (ref "IC8")
      (value "LTC6803-4")
      (footprint "eagle-import:44SSOP")
      (libsource (lib "eagle-import") (part "LTC6803-4"))
    )
    (comp (ref "L5")
      (value "WE-CBF_0603")
      (footprint "eagle-import:0603")
      (libsource (lib "eagle-import") (part "WE-CBF_0603"))
    )
    (comp (ref "L7")
      (value "WE-CBF_0603")
      (footprint "eagle-import:0603")
      (libsource (lib "eagle-import") (part "WE-CBF_0603"))
    )
    (comp (ref "L_V-R")
      (value "100")
      (footprint "eagle-import:R0402")
      (libsource (lib "eagle-import") (part "R0402"))
    )
    (comp (ref "Q1")
      (value "BSS84AKT")
      (footprint "eagle-import:SOT416")
      (libsource (lib "eagle-import") (part "BSS84AKT"))
    )
    (comp (ref "Q2")
      (value "2N7002BKT")
      (footprint "eagle-import:SOT416")
      (libsource (lib "eagle-import") (part "2N7002BKT"))
    )
    (comp (ref "Q5")
      (value "2N7002BKT")
      (footprint "eagle-import:SOT416")
      (libsource (lib "eagle-import") (part "2N7002BKT"))
    )
    (comp (ref "Q6")
      (value "BSS84AKT")
      (footprint "eagle-import:SOT416")
      (libsource (lib "eagle-import") (part "BSS84AKT"))
    )
    (comp (ref "R17")
      (value "1M")
      (footprint "eagle-import:R0402")
      (libsource (lib "eagle-import") (part "R0402"))
    )
    (comp (ref "R18")
      (value "1M")
      (footprint "eagle-import:R0402")
      (libsource (lib "eagle-import") (part "R0402"))
    )
    (comp (ref "R19")
      (value "4.7k")
      (footprint "eagle-import:R0402")
      (libsource (lib "eagle-import") (part "R0402"))
    )
    (comp (ref "R20")
      (value "1M")
      (footprint "eagle-import:R0402")
      (libsource (lib "eagle-import") (part "R0402"))
    )
    (comp (ref "R55")
      (value "1M")
      (footprint "eagle-import:R0402")
      (libsource (lib "eagle-import") (part "R0402"))
    )
    (comp (ref "R56")
      (value "1M")
      (footprint "eagle-import:R0402")
      (libsource (lib "eagle-import") (part "R0402"))
    )
    (comp (ref "R57")
      (value "4.7k")
      (footprint "eagle-import:R0402")
      (libsource (lib "eagle-import") (part "R0402"))
    )
    (comp (ref "R58")
      (value "1M")
      (footprint "eagle-import:R0402")
      (libsource (lib "eagle-import") (part "R0402"))
    )
    (comp (ref "RGQ1_1")
      (value "1M,50V")
      (footprint "eagle-import:R0603")
      (libsource (lib "eagle-import") (part "R0603"))
    )
    (comp (ref "RGQ1_2")
      (value "100k,50V")
      (footprint "eagle-import:R0603")
      (libsource (lib "eagle-import") (part "R0603"))
    )
    (comp (ref "RGQ1_3")
      (value "1M")
      (footprint "eagle-import:R0402")
      (libsource (lib "eagle-import") (part "R0402"))
    )
    (comp (ref "RGQ1_4")
      (value "1M,50V")
      (footprint "eagle-import:R0603")
      (libsource (lib "eagle-import") (part "R0603"))
    )
    (comp (ref "RGQ1_5")
      (value "100k,50V")
      (footprint "eagle-import:R0603")
      (libsource (lib "eagle-import") (part "R0603"))
    )
    (comp (ref "RGQ1_6")
      (value "1M")
      (footprint "eagle-import:R0402")
      (libsource (lib "eagle-import") (part "R0402"))
    )
    (comp (ref "V+R")
      (value "100")
      (footprint "eagle-import:R0402")
      (libsource (lib "eagle-import") (part "R0402"))
    )
    (comp (ref "V+R1")
      (value "100")
      (footprint "eagle-import:R0402")
      (libsource (lib "eagle-import") (part "R0402"))
    )
    (comp (ref "C8")
      (value "10n")
      (footprint "eagle-import:C0402")
      (libsource (lib "eagle-import") (part "C0402"))
    )
    (comp (ref "C10")
      (value "10n")
      (footprint "eagle-import:C0402")
      (libsource (lib "eagle-import") (part "C0402"))
    )
    (comp (ref "C11")
      (value "10n")
      (footprint "eagle-import:C0402")
      (libsource (lib "eagle-import") (part "C0402"))
    )
    (comp (ref "C13")
      (value "10n")
      (footprint "eagle-import:C0402")
      (libsource (lib "eagle-import") (part "C0402"))
    )
    (comp (ref "C14")
      (value "18p")
      (footprint "eagle-import:C0402")
      (libsource (lib "eagle-import") (part "C0402"))
    )
    (comp (ref "C15")
      (value "18p")
      (footprint "eagle-import:C0402")
      (libsource (lib "eagle-import") (part "C0402"))
    )
    (comp (ref "C22")
      (value "100n")
      (footprint "eagle-import:C0402")
      (libsource (lib "eagle-import") (part "C0402"))
    )
    (comp (ref "C23")
      (value "100n")
      (footprint "eagle-import:C0402")
      (libsource (lib "eagle-import") (part "C0402"))
    )
    (comp (ref "C24")
      (value "100n")
      (footprint "eagle-import:C0402")
      (libsource (lib "eagle-import") (part "C0402"))
    )
    (comp (ref "C25")
      (value "18p")
      (footprint "eagle-import:C0402")
      (libsource (lib "eagle-import") (part "C0402"))
    )
    (comp (ref "C31")
      (value "18p")
      (footprint "eagle-import:C0402")
      (libsource (lib "eagle-import") (part "C0402"))
    )
    (comp (ref "C32")
      (value "100n")
      (footprint "eagle-import:C0402")
      (libsource (lib "eagle-import") (part "C0402"))
    )
    (comp (ref "C33")
      (value "100n")
      (footprint "eagle-import:C0402")
      (libsource (lib "eagle-import") (part "C0402"))
    )
    (comp (ref "C34")
      (value "100n")
      (footprint "eagle-import:C0402")
      (libsource (lib "eagle-import") (part "C0402"))
    )
    (comp (ref "IC1")
      (value "LPC11C1X")
      (footprint "eagle-import:LQFP48")
      (libsource (lib "eagle-import") (part "LPC11C1X"))
    )
    (comp (ref "IC7")
      (value "LPC11C1X")
      (footprint "eagle-import:LQFP48")
      (libsource (lib "eagle-import") (part "LPC11C1X"))
    )
    (comp (ref "JP1")
      (value "HEADER-2X31.27")
      (footprint "eagle-import:2X03_1.27MM_SMT")
      (libsource (lib "eagle-import") (part "HEADER-2X31.27"))
    )
    (comp (ref "JP2")
      (value "HEADER-2X31.27")
      (footprint "eagle-import:2X03_1.27MM_SMT")
      (libsource (lib "eagle-import") (part "HEADER-2X31.27"))
    )
    (comp (ref "LED1")
      (value "LED0603")
      (footprint "eagle-import:CHIPLED_0603")
      (libsource (lib "eagle-import") (part "LED0603"))
    )
    (comp (ref "LED2")
      (value "LED0603")
      (footprint "eagle-import:CHIPLED_0603")
      (libsource (lib "eagle-import") (part "LED0603"))
    )
    (comp (ref "Q3")
      (value "2N7002BKT")
      (footprint "eagle-import:SOT416")
      (libsource (lib "eagle-import") (part "2N7002BKT"))
    )
    (comp (ref "Q4")
      (value "2N7002BKT")
      (footprint "eagle-import:SOT416")
      (libsource (lib "eagle-import") (part "2N7002BKT"))
    )
    (comp (ref "R1")
      (value "100")
      (footprint "eagle-import:R0402")
      (libsource (lib "eagle-import") (part "R0402"))
    )
    (comp (ref "R3")
      (value "100")
      (footprint "eagle-import:R0402")
      (libsource (lib "eagle-import") (part "R0402"))
    )
    (comp (ref "R4")
      (value "100")
      (footprint "eagle-import:R0402")
      (libsource (lib "eagle-import") (part "R0402"))
    )
    (comp (ref "R5")
      (value "100")
      (footprint "eagle-import:R0402")
      (libsource (lib "eagle-import") (part "R0402"))
    )
    (comp (ref "R6")
      (value "100")
      (footprint "eagle-import:R0402")
      (libsource (lib "eagle-import") (part "R0402"))
    )
    (comp (ref "R7")
      (value "100")
      (footprint "eagle-import:R0402")
      (libsource (lib "eagle-import") (part "R0402"))
    )
    (comp (ref "R8")
      (value "330")
      (footprint "eagle-import:R0603")
      (libsource (lib "eagle-import") (part "R0603"))
    )
    (comp (ref "R9")
      (value "10k")
      (footprint "eagle-import:R0402")
      (libsource (lib "eagle-import") (part "R0402"))
    )
    (comp (ref "R11")
      (value "10k")
      (footprint "eagle-import:R0402")
      (libsource (lib "eagle-import") (part "R0402"))
    )
    (comp (ref "R15")
      (value "10k")
      (footprint "eagle-import:R0402")
      (libsource (lib "eagle-import") (part "R0402"))
    )
    (comp (ref "R44")
      (value "100")
      (footprint "eagle-import:R0402")
      (libsource (lib "eagle-import") (part "R0402"))
    )
    (comp (ref "R45")
      (value "100")
      (footprint "eagle-import:R0402")
      (libsource (lib "eagle-import") (part "R0402"))
    )
    (comp (ref "R46")
      (value "100")
      (footprint "eagle-import:R0402")
      (libsource (lib "eagle-import") (part "R0402"))
    )
    (comp (ref "R47")
      (value "100")
      (footprint "eagle-import:R0402")
      (libsource (lib "eagle-import") (part "R0402"))
    )
    (comp (ref "R48")
      (value "100")
      (footprint "eagle-import:R0402")
      (libsource (lib "eagle-import") (part "R0402"))
    )
    (comp (ref "R49")
      (value "100")
      (footprint "eagle-import:R0402")
      (libsource (lib "eagle-import") (part "R0402"))
    )
    (comp (ref "R50")
      (value "10k")
      (footprint "eagle-import:R0402")
      (libsource (lib "eagle-import") (part "R0402"))
    )
    (comp (ref "R51")
      (value "10k")
      (footprint "eagle-import:R0402")
      (libsource (lib "eagle-import") (part "R0402"))
    )
    (comp (ref "R52")
      (value "10k")
      (footprint "eagle-import:R0402")
      (libsource (lib "eagle-import") (part "R0402"))
    )
    (comp (ref "R53")
      (value "330")
      (footprint "eagle-import:R0603")
      (libsource (lib "eagle-import") (part "R0603"))
    )
    (comp (ref "Y1")
      (value "CRYSTALTHIN")
      (footprint "eagle-import:CRYSTAL_3.2X2.5")
      (libsource (lib "eagle-import") (part "CRYSTALTHIN"))
    )
    (comp (ref "Y2")
      (value "CRYSTALTHIN")
      (footprint "eagle-import:CRYSTAL_3.2X2.5")
      (libsource (lib "eagle-import") (part "CRYSTALTHIN"))
    )
  )
  (nets
    (net (code "1") (name "BAL1") (class "Default")
      (node (ref "IC2") (pin "25") (pinfunction "S1_25") (pintype "bidirectional"))
      (node (ref "RBG1") (pin "2") (pinfunction "2_2") (pintype "passive"))
    )
    (net (code "2") (name "BAL2") (class "Default")
      (node (ref "IC2") (pin "23") (pinfunction "S2_23") (pintype "bidirectional"))
      (node (ref "RBG2") (pin "2") (pinfunction "2_2") (pintype "passive"))
    )
    (net (code "3") (name "BAL3") (class "Default")
      (node (ref "IC2") (pin "21") (pinfunction "S3_21") (pintype "bidirectional"))
      (node (ref "RBG3") (pin "2") (pinfunction "2_2") (pintype "passive"))
    )
    (net (code "4") (name "BAL4") (class "Default")
      (node (ref "IC2") (pin "19") (pinfunction "S4_19") (pintype "bidirectional"))
      (node (ref "RBG4") (pin "2") (pinfunction "2_2") (pintype "passive"))
    )
    (net (code "5") (name "BAL5") (class "Default")
      (node (ref "IC2") (pin "17") (pinfunction "S5_17") (pintype "bidirectional"))
      (node (ref "RBG5") (pin "2") (pinfunction "2_2") (pintype "passive"))
    )
    (net (code "6") (name "BAL6") (class "Default")
      (node (ref "IC2") (pin "15") (pinfunction "S6_15") (pintype "bidirectional"))
      (node (ref "RBG6") (pin "2") (pinfunction "2_2") (pintype "passive"))
    )
    (net (code "7") (name "BAL7") (class "Default")
      (node (ref "IC2") (pin "13") (pinfunction "S7_13") (pintype "bidirectional"))
      (node (ref "RBG7") (pin "2") (pinfunction "2_2") (pintype "passive"))
    )
    (net (code "8") (name "BAL8") (class "Default")
      (node (ref "IC2") (pin "11") (pinfunction "S8_11") (pintype "bidirectional"))
      (node (ref "RBG8") (pin "2") (pinfunction "2_2") (pintype "passive"))
    )
    (net (code "9") (name "BAL9") (class "Default")
      (node (ref "IC8") (pin "25") (pinfunction "S1_25") (pintype "bidirectional"))
      (node (ref "RBG9") (pin "2") (pinfunction "2_2") (pintype "passive"))
    )
    (net (code "10") (name "BAL10") (class "Default")
      (node (ref "IC8") (pin "23") (pinfunction "S2_23") (pintype "bidirectional"))
      (node (ref "RBG10") (pin "2") (pinfunction "2_2") (pintype "passive"))
    )
    (net (code "11") (name "BAL11") (class "Default")
      (node (ref "IC8") (pin "21") (pinfunction "S3_21") (pintype "bidirectional"))
      (node (ref "RBG11") (pin "2") (pinfunction "2_2") (pintype "passive"))
    )
    (net (code "12") (name "BAL12") (class "Default")
      (node (ref "IC8") (pin "19") (pinfunction "S4_19") (pintype "bidirectional"))
      (node (ref "RBG12") (pin "2") (pinfunction "2_2") (pintype "passive"))
    )
    (net (code "13") (name "BAL13") (class "Default")
      (node (ref "IC8") (pin "17") (pinfunction "S5_17") (pintype "bidirectional"))
      (node (ref "RBG13") (pin "2") (pinfunction "2_2") (pintype "passive"))
    )
    (net (code "14") (name "BAL14") (class "Default")
      (node (ref "IC8") (pin "15") (pinfunction "S6_15") (pintype "bidirectional"))
      (node (ref "RBG14") (pin "2") (pinfunction "2_2") (pintype "passive"))
    )
    (net (code "15") (name "BAL15") (class "Default")
      (node (ref "IC8") (pin "13") (pinfunction "S7_13") (pintype "bidirectional"))
      (node (ref "RBG15") (pin "2") (pinfunction "2_2") (pintype "passive"))
    )
    (net (code "16") (name "BAL16") (class "Default")
      (node (ref "IC8") (pin "11") (pinfunction "S8_11") (pintype "bidirectional"))
      (node (ref "RBG16") (pin "2") (pinfunction "2_2") (pintype "passive"))
    )
    (net (code "17") (name "C0") (class "Default")
      (node (ref "CCM1") (pin "2") (pinfunction "2_2") (pintype "passive"))
      (node (ref "DCM1") (pin "A") (pinfunction "A_A") (pintype "passive"))
      (node (ref "IC2") (pin "26") (pinfunction "C0_26") (pintype "bidirectional"))
      (node (ref "L_V-R") (pin "1") (pinfunction "1_1") (pintype "passive"))
      (node (ref "RP1") (pin "1") (pinfunction "1_1") (pintype "passive"))
      (node (ref "X1") (pin "8") (pinfunction "S_8") (pintype "passive"))
    )
    (net (code "18") (name "C1") (class "Default")
      (node (ref "QB1") (pin "2") (pinfunction "S_2") (pintype "passive"))
      (node (ref "RCM1") (pin "1") (pinfunction "1_1") (pintype "passive"))
      (node (ref "RP2") (pin "1") (pinfunction "1_1") (pintype "passive"))
      (node (ref "X1") (pin "7") (pinfunction "S_7") (pintype "passive"))
    )
    (net (code "19") (name "C1M") (class "Default")
      (node (ref "CCM1") (pin "1") (pinfunction "1_1") (pintype "passive"))
      (node (ref "CCM2") (pin "2") (pinfunction "2_2") (pintype "passive"))
      (node (ref "DCM1") (pin "C") (pinfunction "C_C") (pintype "passive"))
      (node (ref "DCM2") (pin "A") (pinfunction "A_A") (pintype "passive"))
      (node (ref "IC2") (pin "24") (pinfunction "C1_24") (pintype "bidirectional"))
      (node (ref "RCM1") (pin "2") (pinfunction "2_2") (pintype "passive"))
    )
    (net (code "20") (name "C2") (class "Default")
      (node (ref "QB2") (pin "2") (pinfunction "S_2") (pintype "passive"))
      (node (ref "RCM2") (pin "1") (pinfunction "1_1") (pintype "passive"))
      (node (ref "RP3") (pin "1") (pinfunction "1_1") (pintype "passive"))
      (node (ref "X1") (pin "6") (pinfunction "S_6") (pintype "passive"))
    )
    (net (code "21") (name "C2M") (class "Default")
      (node (ref "CCM2") (pin "1") (pinfunction "1_1") (pintype "passive"))
      (node (ref "CCM3") (pin "2") (pinfunction "2_2") (pintype "passive"))
      (node (ref "DCM2") (pin "C") (pinfunction "C_C") (pintype "passive"))
      (node (ref "DCM3") (pin "A") (pinfunction "A_A") (pintype "passive"))
      (node (ref "IC2") (pin "22") (pinfunction "C2_22") (pintype "bidirectional"))
      (node (ref "RCM2") (pin "2") (pinfunction "2_2") (pintype "passive"))
    )
    (net (code "22") (name "C3") (class "Default")
      (node (ref "QB3") (pin "2") (pinfunction "S_2") (pintype "passive"))
      (node (ref "RCM3") (pin "1") (pinfunction "1_1") (pintype "passive"))
      (node (ref "RP4") (pin "1") (pinfunction "1_1") (pintype "passive"))
      (node (ref "X1") (pin "5") (pinfunction "S_5") (pintype "passive"))
    )
    (net (code "23") (name "C3M") (class "Default")
      (node (ref "CCM3") (pin "1") (pinfunction "1_1") (pintype "passive"))
      (node (ref "CCM4") (pin "2") (pinfunction "2_2") (pintype "passive"))
      (node (ref "DCM3") (pin "C") (pinfunction "C_C") (pintype "passive"))
      (node (ref "DCM4") (pin "A") (pinfunction "A_A") (pintype "passive"))
      (node (ref "IC2") (pin "20") (pinfunction "C3_20") (pintype "bidirectional"))
      (node (ref "RCM3") (pin "2") (pinfunction "2_2") (pintype "passive"))
    )
    (net (code "24") (name "C4") (class "Default")
      (node (ref "QB4") (pin "2") (pinfunction "S_2") (pintype "passive"))
      (node (ref "RCM4") (pin "1") (pinfunction "1_1") (pintype "passive"))
      (node (ref "RP5") (pin "1") (pinfunction "1_1") (pintype "passive"))
      (node (ref "X1") (pin "4") (pinfunction "S_4") (pintype "passive"))
    )
    (net (code "25") (name "C4M") (class "Default")
      (node (ref "CCM4") (pin "1") (pinfunction "1_1") (pintype "passive"))
      (node (ref "CCM5") (pin "2") (pinfunction "2_2") (pintype "passive"))
      (node (ref "DCM4") (pin "C") (pinfunction "C_C") (pintype "passive"))
      (node (ref "DCM5") (pin "A") (pinfunction "A_A") (pintype "passive"))
      (node (ref "IC2") (pin "18") (pinfunction "C4_18") (pintype "bidirectional"))
      (node (ref "RCM4") (pin "2") (pinfunction "2_2") (pintype "passive"))
    )
    (net (code "26") (name "C5") (class "Default")
      (node (ref "QB5") (pin "2") (pinfunction "S_2") (pintype "passive"))
      (node (ref "RCM5") (pin "1") (pinfunction "1_1") (pintype "passive"))
      (node (ref "RP6") (pin "1") (pinfunction "1_1") (pintype "passive"))
      (node (ref "X1") (pin "3") (pinfunction "S_3") (pintype "passive"))
    )
    (net (code "27") (name "C5M") (class "Default")
      (node (ref "CCM5") (pin "1") (pinfunction "1_1") (pintype "passive"))
      (node (ref "CCM6") (pin "2") (pinfunction "2_2") (pintype "passive"))
      (node (ref "DCM5") (pin "C") (pinfunction "C_C") (pintype "passive"))
      (node (ref "DCM6") (pin "A") (pinfunction "A_A") (pintype "passive"))
      (node (ref "IC2") (pin "16") (pinfunction "C5_16") (pintype "bidirectional"))
      (node (ref "RCM5") (pin "2") (pinfunction "2_2") (pintype "passive"))
    )
    (net (code "28") (name "C6") (class "Default")
      (node (ref "QB6") (pin "2") (pinfunction "S_2") (pintype "passive"))
      (node (ref "RCM6") (pin "1") (pinfunction "1_1") (pintype "passive"))
      (node (ref "RP7") (pin "1") (pinfunction "1_1") (pintype "passive"))
      (node (ref "X1") (pin "2") (pinfunction "S_2") (pintype "passive"))
    )
    (net (code "29") (name "C6M") (class "Default")
      (node (ref "CCM6") (pin "1") (pinfunction "1_1") (pintype "passive"))
      (node (ref "CCM7") (pin "2") (pinfunction "2_2") (pintype "passive"))
      (node (ref "DCM6") (pin "C") (pinfunction "C_C") (pintype "passive"))
      (node (ref "DCM7") (pin "A") (pinfunction "A_A") (pintype "passive"))
      (node (ref "IC2") (pin "14") (pinfunction "C6_14") (pintype "bidirectional"))
      (node (ref "RCM6") (pin "2") (pinfunction "2_2") (pintype "passive"))
    )
    (net (code "30") (name "C7") (class "Default")
      (node (ref "QB7") (pin "2") (pinfunction "S_2") (pintype "passive"))
      (node (ref "RCM7") (pin "1") (pinfunction "1_1") (pintype "passive"))
      (node (ref "RP8") (pin "1") (pinfunction "1_1") (pintype "passive"))
      (node (ref "X1") (pin "1") (pinfunction "S_1") (pintype "passive"))
    )
    (net (code "31") (name "C7M") (class "Default")
      (node (ref "CCM7") (pin "1") (pinfunction "1_1") (pintype "passive"))
      (node (ref "CCM8") (pin "2") (pinfunction "2_2") (pintype "passive"))
      (node (ref "DCM7") (pin "C") (pinfunction "C_C") (pintype "passive"))
      (node (ref "DCM8") (pin "A") (pinfunction "A_A") (pintype "passive"))
      (node (ref "IC2") (pin "12") (pinfunction "C7_12") (pintype "bidirectional"))
      (node (ref "RCM7") (pin "2") (pinfunction "2_2") (pintype "passive"))
    )
    (net (code "32") (name "C8") (class "Default")
      (node (ref "CCM9") (pin "2") (pinfunction "2_2") (pintype "passive"))
      (node (ref "DCM9") (pin "A") (pinfunction "A_A") (pintype "passive"))
      (node (ref "H_V-R") (pin "1") (pinfunction "1_1") (pintype "passive"))
      (node (ref "IC8") (pin "26") (pinfunction "C0_26") (pintype "bidirectional"))
      (node (ref "L7") (pin "1") (pinfunction "1_1") (pintype "passive"))
      (node (ref "QB8") (pin "2") (pinfunction "S_2") (pintype "passive"))
      (node (ref "RCM8") (pin "1") (pinfunction "1_1") (pintype "passive"))
      (node (ref "RP9") (pin "1") (pinfunction "1_1") (pintype "passive"))
      (node (ref "X4") (pin "9") (pinfunction "S_9") (pintype "passive"))
    )
    (net (code "33") (name "C8M") (class "Default")
      (node (ref "CCM8") (pin "1") (pinfunction "1_1") (pintype "passive"))
      (node (ref "DCM8") (pin "C") (pinfunction "C_C") (pintype "passive"))
      (node (ref "IC2") (pin "10") (pinfunction "C8_10") (pintype "bidirectional"))
      (node (ref "IC2") (pin "2") (pinfunction "C12_2") (pintype "bidirectional"))
      (node (ref "IC2") (pin "4") (pinfunction "C11_4") (pintype "bidirectional"))
      (node (ref "IC2") (pin "6") (pinfunction "C10_6") (pintype "bidirectional"))
      (node (ref "IC2") (pin "8") (pinfunction "C9_8") (pintype "bidirectional"))
      (node (ref "RCM8") (pin "2") (pinfunction "2_2") (pintype "passive"))
    )
    (net (code "34") (name "C9") (class "Default")
      (node (ref "QB9") (pin "2") (pinfunction "S_2") (pintype "passive"))
      (node (ref "RCM9") (pin "1") (pinfunction "1_1") (pintype "passive"))
      (node (ref "RP10") (pin "1") (pinfunction "1_1") (pintype "passive"))
      (node (ref "X4") (pin "8") (pinfunction "S_8") (pintype "passive"))
    )
    (net (code "35") (name "C9M") (class "Default")
      (node (ref "CCM10") (pin "2") (pinfunction "2_2") (pintype "passive"))
      (node (ref "CCM9") (pin "1") (pinfunction "1_1") (pintype "passive"))
      (node (ref "DCM10") (pin "A") (pinfunction "A_A") (pintype "passive"))
      (node (ref "DCM9") (pin "C") (pinfunction "C_C") (pintype "passive"))
      (node (ref "IC8") (pin "24") (pinfunction "C1_24") (pintype "bidirectional"))
      (node (ref "RCM9") (pin "2") (pinfunction "2_2") (pintype "passive"))
    )
    (net (code "36") (name "C10") (class "Default")
      (node (ref "QB10") (pin "2") (pinfunction "S_2") (pintype "passive"))
      (node (ref "RCM10") (pin "1") (pinfunction "1_1") (pintype "passive"))
      (node (ref "RP11") (pin "1") (pinfunction "1_1") (pintype "passive"))
      (node (ref "X4") (pin "7") (pinfunction "S_7") (pintype "passive"))
    )
    (net (code "37") (name "C10M") (class "Default")
      (node (ref "CCM10") (pin "1") (pinfunction "1_1") (pintype "passive"))
      (node (ref "CCM11") (pin "2") (pinfunction "2_2") (pintype "passive"))
      (node (ref "DCM10") (pin "C") (pinfunction "C_C") (pintype "passive"))
      (node (ref "DCM11") (pin "A") (pinfunction "A_A") (pintype "passive"))
      (node (ref "IC8") (pin "22") (pinfunction "C2_22") (pintype "bidirectional"))
      (node (ref "RCM10") (pin "2") (pinfunction "2_2") (pintype "passive"))
    )
    (net (code "38") (name "C11") (class "Default")
      (node (ref "QB11") (pin "2") (pinfunction "S_2") (pintype "passive"))
      (node (ref "RCM11") (pin "1") (pinfunction "1_1") (pintype "passive"))
      (node (ref "RP12") (pin "1") (pinfunction "1_1") (pintype "passive"))
      (node (ref "X4") (pin "6") (pinfunction "S_6") (pintype "passive"))
    )
    (net (code "39") (name "C11M") (class "Default")
      (node (ref "CCM11") (pin "1") (pinfunction "1_1") (pintype "passive"))
      (node (ref "CCM12") (pin "2") (pinfunction "2_2") (pintype "passive"))
      (node (ref "DCM11") (pin "C") (pinfunction "C_C") (pintype "passive"))
      (node (ref "DCM12") (pin "A") (pinfunction "A_A") (pintype "passive"))
      (node (ref "IC8") (pin "20") (pinfunction "C3_20") (pintype "bidirectional"))
      (node (ref "RCM11") (pin "2") (pinfunction "2_2") (pintype "passive"))
    )
    (net (code "40") (name "C12") (class "Default")
      (node (ref "QB12") (pin "2") (pinfunction "S_2") (pintype "passive"))
      (node (ref "RCM12") (pin "1") (pinfunction "1_1") (pintype "passive"))
      (node (ref "RP13") (pin "1") (pinfunction "1_1") (pintype "passive"))
      (node (ref "X4") (pin "5") (pinfunction "S_5") (pintype "passive"))
    )
    (net (code "41") (name "C12M") (class "Default")
      (node (ref "CCM12") (pin "1") (pinfunction "1_1") (pintype "passive"))
      (node (ref "CCM13") (pin "2") (pinfunction "2_2") (pintype "passive"))
      (node (ref "DCM12") (pin "C") (pinfunction "C_C") (pintype "passive"))
      (node (ref "DCM13") (pin "A") (pinfunction "A_A") (pintype "passive"))
      (node (ref "IC8") (pin "18") (pinfunction "C4_18") (pintype "bidirectional"))
      (node (ref "RCM12") (pin "2") (pinfunction "2_2") (pintype "passive"))
    )
    (net (code "42") (name "C13") (class "Default")
      (node (ref "QB13") (pin "2") (pinfunction "S_2") (pintype "passive"))
      (node (ref "RCM13") (pin "1") (pinfunction "1_1") (pintype "passive"))
      (node (ref "RP14") (pin "1") (pinfunction "1_1") (pintype "passive"))
      (node (ref "X4") (pin "4") (pinfunction "S_4") (pintype "passive"))
    )
    (net (code "43") (name "C13M") (class "Default")
      (node (ref "CCM13") (pin "1") (pinfunction "1_1") (pintype "passive"))
      (node (ref "CCM14") (pin "2") (pinfunction "2_2") (pintype "passive"))
      (node (ref "DCM13") (pin "C") (pinfunction "C_C") (pintype "passive"))
      (node (ref "DCM14") (pin "A") (pinfunction "A_A") (pintype "passive"))
      (node (ref "IC8") (pin "16") (pinfunction "C5_16") (pintype "bidirectional"))
      (node (ref "RCM13") (pin "2") (pinfunction "2_2") (pintype "passive"))
    )
    (net (code "44") (name "C14") (class "Default")
      (node (ref "QB14") (pin "2") (pinfunction "S_2") (pintype "passive"))
      (node (ref "RCM14") (pin "1") (pinfunction "1_1") (pintype "passive"))
      (node (ref "RP15") (pin "1") (pinfunction "1_1") (pintype "passive"))
      (node (ref "X4") (pin "3") (pinfunction "S_3") (pintype "passive"))
    )
    (net (code "45") (name "C14M") (class "Default")
      (node (ref "CCM14") (pin "1") (pinfunction "1_1") (pintype "passive"))
      (node (ref "CCM15") (pin "2") (pinfunction "2_2") (pintype "passive"))
      (node (ref "DCM14") (pin "C") (pinfunction "C_C") (pintype "passive"))
      (node (ref "DCM15") (pin "A") (pinfunction "A_A") (pintype "passive"))
      (node (ref "IC8") (pin "14") (pinfunction "C6_14") (pintype "bidirectional"))
      (node (ref "RCM14") (pin "2") (pinfunction "2_2") (pintype "passive"))
    )
    (net (code "46") (name "C15") (class "Default")
      (node (ref "QB15") (pin "2") (pinfunction "S_2") (pintype "passive"))
      (node (ref "RCM15") (pin "1") (pinfunction "1_1") (pintype "passive"))
      (node (ref "RP16") (pin "1") (pinfunction "1_1") (pintype "passive"))
      (node (ref "X4") (pin "2") (pinfunction "S_2") (pintype "passive"))
    )
    (net (code "47") (name "C15M") (class "Default")
      (node (ref "CCM15") (pin "1") (pinfunction "1_1") (pintype "passive"))
      (node (ref "CCM16") (pin "2") (pinfunction "2_2") (pintype "passive"))
      (node (ref "DCM15") (pin "C") (pinfunction "C_C") (pintype "passive"))
      (node (ref "DCM16") (pin "A") (pinfunction "A_A") (pintype "passive"))
      (node (ref "IC8") (pin "12") (pinfunction "C7_12") (pintype "bidirectional"))
      (node (ref "RCM15") (pin "2") (pinfunction "2_2") (pintype "passive"))
    )
    (net (code "48") (name "C16") (class "Default")
      (node (ref "L5") (pin "1") (pinfunction "1_1") (pintype "passive"))
      (node (ref "QB16") (pin "2") (pinfunction "S_2") (pintype "passive"))
      (node (ref "RCM16") (pin "1") (pinfunction "1_1") (pintype "passive"))
      (node (ref "X4") (pin "1") (pinfunction "S_1") (pintype "passive"))
    )
    (net (code "49") (name "C16M") (class "Default")
      (node (ref "CCM16") (pin "1") (pinfunction "1_1") (pintype "passive"))
      (node (ref "DCM16") (pin "C") (pinfunction "C_C") (pintype "passive"))
      (node (ref "IC8") (pin "10") (pinfunction "C8_10") (pintype "bidirectional"))
      (node (ref "IC8") (pin "2") (pinfunction "C12_2") (pintype "bidirectional"))
      (node (ref "IC8") (pin "4") (pinfunction "C11_4") (pintype "bidirectional"))
      (node (ref "IC8") (pin "6") (pinfunction "C10_6") (pintype "bidirectional"))
      (node (ref "IC8") (pin "8") (pinfunction "C9_8") (pintype "bidirectional"))
      (node (ref "RCM16") (pin "2") (pinfunction "2_2") (pintype "passive"))
    )
    (net (code "50") (name "CANH") (class "Default")
      (node (ref "L11") (pin "1") (pinfunction "1_1") (pintype "passive"))
      (node (ref "L8") (pin "1") (pinfunction "1_1") (pintype "passive"))
      (node (ref "SJ1") (pin "2") (pinfunction "2_2") (pintype "passive"))
      (node (ref "X3") (pin "3") (pinfunction "S_3") (pintype "passive"))
      (node (ref "X6") (pin "3") (pinfunction "S_3") (pintype "passive"))
    )
    (net (code "51") (name "CANL") (class "Default")
      (node (ref "L11") (pin "3") (pinfunction "3_3") (pintype "passive"))
      (node (ref "L8") (pin "3") (pinfunction "3_3") (pintype "passive"))
      (node (ref "R22") (pin "2") (pinfunction "2_2") (pintype "passive"))
      (node (ref "X3") (pin "4") (pinfunction "S_4") (pintype "passive"))
      (node (ref "X6") (pin "4") (pinfunction "S_4") (pintype "passive"))
    )
    (net (code "52") (name "CAR+12V") (class "Default")
      (node (ref "C3") (pin "1") (pinfunction "1_1") (pintype "passive"))
      (node (ref "DCIN") (pin "1") (pinfunction "VI_1") (pintype "bidirectional"))
      (node (ref "L1") (pin "1") (pinfunction "1_1") (pintype "passive"))
    )
    (net (code "53") (name "CAR+12VIN") (class "Default")
      (node (ref "C2") (pin "1") (pinfunction "1_1") (pintype "passive"))
      (node (ref "L1") (pin "2") (pinfunction "2_2") (pintype "passive"))
      (node (ref "X3") (pin "1") (pinfunction "S_1") (pintype "passive"))
      (node (ref "X3") (pin "2") (pinfunction "S_2") (pintype "passive"))
      (node (ref "X6") (pin "1") (pinfunction "S_1") (pintype "passive"))
      (node (ref "X6") (pin "2") (pinfunction "S_2") (pintype "passive"))
    )
    (net (code "54") (name "CARGND") (class "Default")
      (node (ref "C16") (pin "2") (pinfunction "2_2") (pintype "passive"))
      (node (ref "C18") (pin "2") (pinfunction "2_2") (pintype "passive"))
      (node (ref "C3") (pin "2") (pinfunction "2_2") (pintype "passive"))
      (node (ref "C6") (pin "2") (pinfunction "2_2") (pintype "passive"))
      (node (ref "C7") (pin "2") (pinfunction "2_2") (pintype "passive"))
      (node (ref "DCDC1") (pin "1") (pinfunction "VIN-_1") (pintype "bidirectional"))
      (node (ref "DCIN") (pin "2") (pinfunction "GND_2") (pintype "bidirectional"))
      (node (ref "IC3") (pin "4") (pinfunction "GND1_4") (pintype "bidirectional"))
      (node (ref "IC4") (pin "2") (pinfunction "VSS_2") (pintype "bidirectional"))
      (node (ref "L9") (pin "1") (pinfunction "1_1") (pintype "passive"))
      (node (ref "R12") (pin "2") (pinfunction "2_2") (pintype "passive"))
    )
    (net (code "55") (name "CARGNDIN") (class "Default")
      (node (ref "C2") (pin "2") (pinfunction "2_2") (pintype "passive"))
      (node (ref "L6") (pin "2") (pinfunction "2_2") (pintype "passive"))
      (node (ref "L9") (pin "2") (pinfunction "2_2") (pintype "passive"))
      (node (ref "X3") (pin "5") (pinfunction "S_5") (pintype "passive"))
      (node (ref "X3") (pin "6") (pinfunction "S_6") (pintype "passive"))
      (node (ref "X6") (pin "5") (pinfunction "S_5") (pintype "passive"))
      (node (ref "X6") (pin "6") (pinfunction "S_6") (pintype "passive"))
    )
    (net (code "56") (name "H+3V3") (class "Default")
      (node (ref "C13") (pin "1") (pinfunction "1_1") (pintype "passive"))
      (node (ref "C32") (pin "1") (pinfunction "1_1") (pintype "passive"))
      (node (ref "C33") (pin "1") (pinfunction "1_1") (pintype "passive"))
      (node (ref "C5") (pin "1") (pinfunction "1_1") (pintype "passive"))
      (node (ref "C8") (pin "1") (pinfunction "1_1") (pintype "passive"))
      (node (ref "C9") (pin "1") (pinfunction "1_1") (pintype "passive"))
      (node (ref "IC3") (pin "8") (pinfunction "VDD2_8") (pintype "bidirectional"))
      (node (ref "IC7") (pin "44") (pinfunction "VDD_44") (pintype "bidirectional"))
      (node (ref "IC7") (pin "8") (pinfunction "VDD_8") (pintype "bidirectional"))
      (node (ref "IC8") (pin "30") (pinfunction "VTEMP2_30") (pintype "bidirectional"))
      (node (ref "JP2") (pin "2") (pinfunction "2_2") (pintype "passive"))
      (node (ref "L2") (pin "1") (pinfunction "1_1") (pintype "passive"))
      (node (ref "LED1") (pin "A") (pinfunction "A_A") (pintype "passive"))
      (node (ref "LED19") (pin "A") (pinfunction "A_A") (pintype "passive"))
      (node (ref "NTC_R1") (pin "2") (pinfunction "2_2") (pintype "passive"))
      (node (ref "NTC_R2") (pin "2") (pinfunction "2_2") (pintype "passive"))
      (node (ref "Q5") (pin "1") (pinfunction "G_1") (pintype "passive"))
      (node (ref "R51") (pin "1") (pinfunction "1_1") (pintype "passive"))
      (node (ref "R9") (pin "1") (pinfunction "1_1") (pintype "passive"))
      (node (ref "RGQ1_6") (pin "2") (pinfunction "2_2") (pintype "passive"))
    )
    (net (code "57") (name "HGND") (class "Default")
      (node (ref "C13") (pin "2") (pinfunction "2_2") (pintype "passive"))
      (node (ref "C24") (pin "2") (pinfunction "2_2") (pintype "passive"))
      (node (ref "C25") (pin "1") (pinfunction "1_1") (pintype "passive"))
      (node (ref "C31") (pin "1") (pinfunction "1_1") (pintype "passive"))
      (node (ref "C32") (pin "2") (pinfunction "2_2") (pintype "passive"))
      (node (ref "C33") (pin "2") (pinfunction "2_2") (pintype "passive"))
      (node (ref "C35") (pin "2") (pinfunction "2_2") (pintype "passive"))
      (node (ref "C4") (pin "2") (pinfunction "2_2") (pintype "passive"))
      (node (ref "C5") (pin "2") (pinfunction "2_2") (pintype "passive"))
      (node (ref "C8") (pin "2") (pinfunction "2_2") (pintype "passive"))
      (node (ref "C9") (pin "2") (pinfunction "2_2") (pintype "passive"))
      (node (ref "CFSM1") (pin "1") (pinfunction "1_1") (pintype "passive"))
      (node (ref "CVREF1") (pin "1") (pinfunction "1_1") (pintype "passive"))
      (node (ref "CVREG1") (pin "1") (pinfunction "1_1") (pintype "passive"))
      (node (ref "D3") (pin "A") (pinfunction "A_A") (pintype "passive"))
      (node (ref "DCDC1") (pin "4") (pinfunction "VOUT-_4") (pintype "bidirectional"))
      (node (ref "H_V-R") (pin "2") (pinfunction "2_2") (pintype "passive"))
      (node (ref "IC3") (pin "5") (pinfunction "GND2_5") (pintype "bidirectional"))
      (node (ref "IC7") (pin "41") (pinfunction "VSS_41") (pintype "bidirectional"))
      (node (ref "IC7") (pin "5") (pinfunction "VSS_5") (pintype "bidirectional"))
      (node (ref "IC8") (pin "27") (pinfunction "V-_27") (pintype "bidirectional"))
      (node (ref "IC8") (pin "33") (pinfunction "TOS_33") (pintype "bidirectional"))
      (node (ref "IC8") (pin "34") (pinfunction "WDTB_34") (pintype "bidirectional"))
      (node (ref "IC8") (pin "35") (pinfunction "GPIO1_35") (pintype "bidirectional"))
      (node (ref "IC8") (pin "36") (pinfunction "GPIO2_36") (pintype "bidirectional"))
      (node (ref "IC8") (pin "37") (pinfunction "A0_37") (pintype "bidirectional"))
      (node (ref "IC8") (pin "38") (pinfunction "A1_38") (pintype "bidirectional"))
      (node (ref "IC8") (pin "39") (pinfunction "A2_39") (pintype "bidirectional"))
      (node (ref "IC8") (pin "40") (pinfunction "A3_40") (pintype "bidirectional"))
      (node (ref "JP2") (pin "6") (pinfunction "6_6") (pintype "passive"))
      (node (ref "NTC_C1") (pin "2") (pinfunction "2_2") (pintype "passive"))
      (node (ref "NTC_C2") (pin "2") (pinfunction "2_2") (pintype "passive"))
      (node (ref "Q3") (pin "2") (pinfunction "S_2") (pintype "passive"))
      (node (ref "Q5") (pin "2") (pinfunction "S_2") (pintype "passive"))
      (node (ref "R16") (pin "1") (pinfunction "1_1") (pintype "passive"))
      (node (ref "R43") (pin "1") (pinfunction "1_1") (pintype "passive"))
      (node (ref "R50") (pin "1") (pinfunction "1_1") (pintype "passive"))
      (node (ref "RGQ1_6") (pin "1") (pinfunction "1_1") (pintype "passive"))
      (node (ref "X2") (pin "1") (pinfunction "S_1") (pintype "passive"))
      (node (ref "X2") (pin "3") (pinfunction "S_3") (pintype "passive"))
    )
    (net (code "58") (name "H_AD1") (class "Default")
      (node (ref "IC7") (pin "33") (pinfunction "PIO1_0/AD1/CT32B1_CAP0_33") (pintype "bidirectional"))
      (node (ref "NTC_C1") (pin "1") (pinfunction "1_1") (pintype "passive"))
      (node (ref "NTC_R1") (pin "1") (pinfunction "1_1") (pintype "passive"))
      (node (ref "X2") (pin "2") (pinfunction "S_2") (pintype "passive"))
    )
    (net (code "59") (name "H_AD2") (class "Default")
      (node (ref "IC7") (pin "34") (pinfunction "PIO1_1/AD2/CT32B1_MAT0_34") (pintype "bidirectional"))
      (node (ref "NTC_C2") (pin "1") (pinfunction "1_1") (pintype "passive"))
      (node (ref "NTC_R2") (pin "1") (pinfunction "1_1") (pintype "passive"))
      (node (ref "X2") (pin "4") (pinfunction "S_4") (pintype "passive"))
    )
    (net (code "60") (name "H_CANRX") (class "Default")
      (node (ref "IC3") (pin "6") (pinfunction "O2_6") (pintype "bidirectional"))
      (node (ref "R49") (pin "2") (pinfunction "2_2") (pintype "passive"))
    )
    (net (code "61") (name "H_CANTX") (class "Default")
      (node (ref "IC3") (pin "7") (pinfunction "I1_7") (pintype "bidirectional"))
      (node (ref "R48") (pin "2") (pinfunction "2_2") (pintype "passive"))
    )
    (net (code "62") (name "H_CSB") (class "Default")
      (node (ref "IC8") (pin "44") (pinfunction "CSBI_44") (pintype "bidirectional"))
      (node (ref "R44") (pin "2") (pinfunction "2_2") (pintype "passive"))
      (node (ref "R58") (pin "1") (pinfunction "1_1") (pintype "passive"))
    )
    (net (code "63") (name "H_FSM") (class "Default")
      (node (ref "CFSM1") (pin "2") (pinfunction "2_2") (pintype "passive"))
      (node (ref "IC8") (pin "29") (pinfunction "VTEMP1_29") (pintype "bidirectional"))
      (node (ref "R10") (pin "1") (pinfunction "1_1") (pintype "passive"))
      (node (ref "R16") (pin "2") (pinfunction "2_2") (pintype "passive"))
    )
    (net (code "64") (name "H_ISP_CAN") (class "Default")
      (node (ref "IC7") (pin "14") (pinfunction "PIO0_3_14") (pintype "bidirectional"))
      (node (ref "R50") (pin "2") (pinfunction "2_2") (pintype "passive"))
    )
    (net (code "65") (name "H_ISP_ENTER") (class "Default")
      (node (ref "IC7") (pin "4") (pinfunction "PIO0_1/CLKOUT/CT32B0_MAT2_4") (pintype "bidirectional"))
      (node (ref "JP2") (pin "5") (pinfunction "5_5") (pintype "passive"))
      (node (ref "R51") (pin "2") (pinfunction "2_2") (pintype "passive"))
    )
    (net (code "66") (name "H_LED") (class "Default")
      (node (ref "IC7") (pin "48") (pinfunction "PIO3_3/~{RI}_48") (pintype "bidirectional"))
      (node (ref "Q3") (pin "1") (pinfunction "G_1") (pintype "passive"))
    )
    (net (code "67") (name "H_SCK") (class "Default")
      (node (ref "IC8") (pin "41") (pinfunction "SCKI_41") (pintype "bidirectional"))
      (node (ref "R45") (pin "2") (pinfunction "2_2") (pintype "passive"))
      (node (ref "R55") (pin "1") (pinfunction "1_1") (pintype "passive"))
    )
    (net (code "68") (name "H_SDI") (class "Default")
      (node (ref "IC8") (pin "42") (pinfunction "SDI_42") (pintype "bidirectional"))
      (node (ref "R47") (pin "2") (pinfunction "2_2") (pintype "passive"))
      (node (ref "R56") (pin "1") (pinfunction "1_1") (pintype "passive"))
    )
    (net (code "69") (name "H_SDO") (class "Default")
      (node (ref "IC8") (pin "43") (pinfunction "SDO_43") (pintype "bidirectional"))
      (node (ref "R46") (pin "2") (pinfunction "2_2") (pintype "passive"))
      (node (ref "R57") (pin "1") (pinfunction "1_1") (pintype "passive"))
    )
    (net (code "70") (name "H_SWCLK") (class "Default")
      (node (ref "IC7") (pin "29") (pinfunction "PIO0_10/SWCLK/SCK0/CT16B0_MAT2_29") (pintype "bidirectional"))
      (node (ref "JP2") (pin "4") (pinfunction "4_4") (pintype "passive"))
    )
    (net (code "71") (name "H_SWDIO") (class "Default")
      (node (ref "IC7") (pin "39") (pinfunction "PIO1_3/SWDIO/AD4/CT32B1_MAT2_39") (pintype "bidirectional"))
      (node (ref "JP2") (pin "3") (pinfunction "3_3") (pintype "passive"))
    )
    (net (code "72") (name "H_V+") (class "Default")
      (node (ref "C35") (pin "1") (pinfunction "1_1") (pintype "passive"))
      (node (ref "D3") (pin "C") (pinfunction "C_C") (pintype "passive"))
      (node (ref "IC8") (pin "1") (pinfunction "V+_1") (pintype "bidirectional"))
      (node (ref "Q6") (pin "3") (pinfunction "D_3") (pintype "passive"))
      (node (ref "R10") (pin "2") (pinfunction "2_2") (pintype "passive"))
    )
    (net (code "73") (name "H_VREF") (class "Default")
      (node (ref "CVREF1") (pin "2") (pinfunction "2_2") (pintype "passive"))
      (node (ref "IC8") (pin "31") (pinfunction "VREF_31") (pintype "bidirectional"))
    )
    (net (code "74") (name "H_VREG") (class "Default")
      (node (ref "CVREG1") (pin "2") (pinfunction "2_2") (pintype "passive"))
      (node (ref "IC8") (pin "32") (pinfunction "VREG_32") (pintype "bidirectional"))
      (node (ref "R55") (pin "2") (pinfunction "2_2") (pintype "passive"))
      (node (ref "R56") (pin "2") (pinfunction "2_2") (pintype "passive"))
      (node (ref "R57") (pin "2") (pinfunction "2_2") (pintype "passive"))
      (node (ref "R58") (pin "2") (pinfunction "2_2") (pintype "passive"))
    )
    (net (code "75") (name "H_~{RESET}") (class "Default")
      (node (ref "C24") (pin "1") (pinfunction "1_1") (pintype "passive"))
      (node (ref "IC7") (pin "3") (pinfunction "PIO0_0/~{RESET}_3") (pintype "bidirectional"))
      (node (ref "JP2") (pin "1") (pinfunction "1_1") (pintype "passive"))
      (node (ref "R9") (pin "2") (pinfunction "2_2") (pintype "passive"))
    )
    (net (code "76") (name "L+3V3") (class "Default")
      (node (ref "C10") (pin "1") (pinfunction "1_1") (pintype "passive"))
      (node (ref "C11") (pin "1") (pinfunction "1_1") (pintype "passive"))
      (node (ref "C22") (pin "1") (pinfunction "1_1") (pintype "passive"))
      (node (ref "C23") (pin "1") (pinfunction "1_1") (pintype "passive"))
      (node (ref "C27") (pin "1") (pinfunction "1_1") (pintype "passive"))
      (node (ref "C30") (pin "1") (pinfunction "1_1") (pintype "passive"))
      (node (ref "IC1") (pin "44") (pinfunction "VDD_44") (pintype "bidirectional"))
      (node (ref "IC1") (pin "8") (pinfunction "VDD_8") (pintype "bidirectional"))
      (node (ref "IC2") (pin "30") (pinfunction "VTEMP2_30") (pintype "bidirectional"))
      (node (ref "IC6") (pin "8") (pinfunction "VDD2_8") (pintype "bidirectional"))
      (node (ref "JP1") (pin "2") (pinfunction "2_2") (pintype "passive"))
      (node (ref "L12") (pin "1") (pinfunction "1_1") (pintype "passive"))
      (node (ref "LED18") (pin "A") (pinfunction "A_A") (pintype "passive"))
      (node (ref "LED2") (pin "A") (pinfunction "A_A") (pintype "passive"))
      (node (ref "NTC_R3") (pin "2") (pinfunction "2_2") (pintype "passive"))
      (node (ref "NTC_R4") (pin "2") (pinfunction "2_2") (pintype "passive"))
      (node (ref "Q2") (pin "1") (pinfunction "G_1") (pintype "passive"))
      (node (ref "R15") (pin "1") (pinfunction "1_1") (pintype "passive"))
      (node (ref "R52") (pin "1") (pinfunction "1_1") (pintype "passive"))
      (node (ref "RGQ1_3") (pin "2") (pinfunction "2_2") (pintype "passive"))
    )
    (net (code "77") (name "LGND") (class "Default")
      (node (ref "C1") (pin "2") (pinfunction "2_2") (pintype "passive"))
      (node (ref "C10") (pin "2") (pinfunction "2_2") (pintype "passive"))
      (node (ref "C11") (pin "2") (pinfunction "2_2") (pintype "passive"))
      (node (ref "C14") (pin "1") (pinfunction "1_1") (pintype "passive"))
      (node (ref "C15") (pin "1") (pinfunction "1_1") (pintype "passive"))
      (node (ref "C22") (pin "2") (pinfunction "2_2") (pintype "passive"))
      (node (ref "C23") (pin "2") (pinfunction "2_2") (pintype "passive"))
      (node (ref "C27") (pin "2") (pinfunction "2_2") (pintype "passive"))
      (node (ref "C29") (pin "2") (pinfunction "2_2") (pintype "passive"))
      (node (ref "C30") (pin "2") (pinfunction "2_2") (pintype "passive"))
      (node (ref "C34") (pin "2") (pinfunction "2_2") (pintype "passive"))
      (node (ref "CFSM") (pin "1") (pinfunction "1_1") (pintype "passive"))
      (node (ref "CVREF") (pin "1") (pinfunction "1_1") (pintype "passive"))
      (node (ref "CVREG") (pin "1") (pinfunction "1_1") (pintype "passive"))
      (node (ref "D1") (pin "A") (pinfunction "A_A") (pintype "passive"))
      (node (ref "DCDC2") (pin "4") (pinfunction "VOUT-_4") (pintype "bidirectional"))
      (node (ref "IC1") (pin "41") (pinfunction "VSS_41") (pintype "bidirectional"))
      (node (ref "IC1") (pin "5") (pinfunction "VSS_5") (pintype "bidirectional"))
      (node (ref "IC2") (pin "27") (pinfunction "V-_27") (pintype "bidirectional"))
      (node (ref "IC2") (pin "33") (pinfunction "TOS_33") (pintype "bidirectional"))
      (node (ref "IC2") (pin "34") (pinfunction "WDTB_34") (pintype "bidirectional"))
      (node (ref "IC2") (pin "35") (pinfunction "GPIO1_35") (pintype "bidirectional"))
      (node (ref "IC2") (pin "36") (pinfunction "GPIO2_36") (pintype "bidirectional"))
      (node (ref "IC2") (pin "37") (pinfunction "A0_37") (pintype "bidirectional"))
      (node (ref "IC2") (pin "38") (pinfunction "A1_38") (pintype "bidirectional"))
      (node (ref "IC2") (pin "39") (pinfunction "A2_39") (pintype "bidirectional"))
      (node (ref "IC2") (pin "40") (pinfunction "A3_40") (pintype "bidirectional"))
      (node (ref "IC6") (pin "5") (pinfunction "GND2_5") (pintype "bidirectional"))
      (node (ref "JP1") (pin "6") (pinfunction "6_6") (pintype "passive"))
      (node (ref "L_V-R") (pin "2") (pinfunction "2_2") (pintype "passive"))
      (node (ref "NTC_C3") (pin "2") (pinfunction "2_2") (pintype "passive"))
      (node (ref "NTC_C4") (pin "2") (pinfunction "2_2") (pintype "passive"))
      (node (ref "Q2") (pin "2") (pinfunction "S_2") (pintype "passive"))
      (node (ref "Q4") (pin "2") (pinfunction "S_2") (pintype "passive"))
      (node (ref "R11") (pin "1") (pinfunction "1_1") (pintype "passive"))
      (node (ref "R42") (pin "1") (pinfunction "1_1") (pintype "passive"))
      (node (ref "R60") (pin "1") (pinfunction "1_1") (pintype "passive"))
      (node (ref "RGQ1_3") (pin "1") (pinfunction "1_1") (pintype "passive"))
      (node (ref "X5") (pin "1") (pinfunction "S_1") (pintype "passive"))
      (node (ref "X5") (pin "3") (pinfunction "S_3") (pintype "passive"))
    )
    (net (code "78") (name "L_AD1") (class "Default")
      (node (ref "IC1") (pin "33") (pinfunction "PIO1_0/AD1/CT32B1_CAP0_33") (pintype "bidirectional"))
      (node (ref "NTC_C3") (pin "1") (pinfunction "1_1") (pintype "passive"))
      (node (ref "NTC_R3") (pin "1") (pinfunction "1_1") (pintype "passive"))
      (node (ref "X5") (pin "2") (pinfunction "S_2") (pintype "passive"))
    )
    (net (code "79") (name "L_AD2") (class "Default")
      (node (ref "IC1") (pin "34") (pinfunction "PIO1_1/AD2/CT32B1_MAT0_34") (pintype "bidirectional"))
      (node (ref "NTC_C4") (pin "1") (pinfunction "1_1") (pintype "passive"))
      (node (ref "NTC_R4") (pin "1") (pinfunction "1_1") (pintype "passive"))
      (node (ref "X5") (pin "4") (pinfunction "S_4") (pintype "passive"))
    )
    (net (code "80") (name "L_CANRX") (class "Default")
      (node (ref "IC6") (pin "6") (pinfunction "O2_6") (pintype "bidirectional"))
      (node (ref "R7") (pin "2") (pinfunction "2_2") (pintype "passive"))
    )
    (net (code "81") (name "L_CANTX") (class "Default")
      (node (ref "IC6") (pin "7") (pinfunction "I1_7") (pintype "bidirectional"))
      (node (ref "R6") (pin "2") (pinfunction "2_2") (pintype "passive"))
    )
    (net (code "82") (name "L_CSB") (class "Default")
      (node (ref "IC2") (pin "44") (pinfunction "CSBI_44") (pintype "bidirectional"))
      (node (ref "R1") (pin "2") (pinfunction "2_2") (pintype "passive"))
      (node (ref "R20") (pin "1") (pinfunction "1_1") (pintype "passive"))
    )
    (net (code "83") (name "L_FSM") (class "Default")
      (node (ref "CFSM") (pin "2") (pinfunction "2_2") (pintype "passive"))
      (node (ref "IC2") (pin "29") (pinfunction "VTEMP1_29") (pintype "bidirectional"))
      (node (ref "R59") (pin "1") (pinfunction "1_1") (pintype "passive"))
      (node (ref "R60") (pin "2") (pinfunction "2_2") (pintype "passive"))
    )
    (net (code "84") (name "L_ISP_CAN") (class "Default")
      (node (ref "IC1") (pin "14") (pinfunction "PIO0_3_14") (pintype "bidirectional"))
      (node (ref "R11") (pin "2") (pinfunction "2_2") (pintype "passive"))
    )
    (net (code "85") (name "L_ISP_ENTER") (class "Default")
      (node (ref "IC1") (pin "4") (pinfunction "PIO0_1/CLKOUT/CT32B0_MAT2_4") (pintype "bidirectional"))
      (node (ref "JP1") (pin "5") (pinfunction "5_5") (pintype "passive"))
      (node (ref "R15") (pin "2") (pinfunction "2_2") (pintype "passive"))
    )
    (net (code "86") (name "L_LED") (class "Default")
      (node (ref "IC1") (pin "48") (pinfunction "PIO3_3/~{RI}_48") (pintype "bidirectional"))
      (node (ref "Q4") (pin "1") (pinfunction "G_1") (pintype "passive"))
    )
    (net (code "87") (name "L_SCK") (class "Default")
      (node (ref "IC2") (pin "41") (pinfunction "SCKI_41") (pintype "bidirectional"))
      (node (ref "R17") (pin "1") (pinfunction "1_1") (pintype "passive"))
      (node (ref "R3") (pin "2") (pinfunction "2_2") (pintype "passive"))
    )
    (net (code "88") (name "L_SDI") (class "Default")
      (node (ref "IC2") (pin "42") (pinfunction "SDI_42") (pintype "bidirectional"))
      (node (ref "R18") (pin "1") (pinfunction "1_1") (pintype "passive"))
      (node (ref "R5") (pin "2") (pinfunction "2_2") (pintype "passive"))
    )
    (net (code "89") (name "L_SDO") (class "Default")
      (node (ref "IC2") (pin "43") (pinfunction "SDO_43") (pintype "bidirectional"))
      (node (ref "R19") (pin "1") (pinfunction "1_1") (pintype "passive"))
      (node (ref "R4") (pin "2") (pinfunction "2_2") (pintype "passive"))
    )
    (net (code "90") (name "L_SWCLK") (class "Default")
      (node (ref "IC1") (pin "29") (pinfunction "PIO0_10/SWCLK/SCK0/CT16B0_MAT2_29") (pintype "bidirectional"))
      (node (ref "JP1") (pin "4") (pinfunction "4_4") (pintype "passive"))
    )
    (net (code "91") (name "L_SWDIO") (class "Default")
      (node (ref "IC1") (pin "39") (pinfunction "PIO1_3/SWDIO/AD4/CT32B1_MAT2_39") (pintype "bidirectional"))
      (node (ref "JP1") (pin "3") (pinfunction "3_3") (pintype "passive"))
    )
    (net (code "92") (name "L_V+") (class "Default")
      (node (ref "C1") (pin "1") (pinfunction "1_1") (pintype "passive"))
      (node (ref "D1") (pin "C") (pinfunction "C_C") (pintype "passive"))
      (node (ref "IC2") (pin "1") (pinfunction "V+_1") (pintype "bidirectional"))
      (node (ref "Q1") (pin "3") (pinfunction "D_3") (pintype "passive"))
      (node (ref "R59") (pin "2") (pinfunction "2_2") (pintype "passive"))
    )
    (net (code "93") (name "L_VREF") (class "Default")
      (node (ref "CVREF") (pin "2") (pinfunction "2_2") (pintype "passive"))
      (node (ref "IC2") (pin "31") (pinfunction "VREF_31") (pintype "bidirectional"))
    )
    (net (code "94") (name "L_VREG") (class "Default")
      (node (ref "CVREG") (pin "2") (pinfunction "2_2") (pintype "passive"))
      (node (ref "IC2") (pin "32") (pinfunction "VREG_32") (pintype "bidirectional"))
      (node (ref "R17") (pin "2") (pinfunction "2_2") (pintype "passive"))
      (node (ref "R18") (pin "2") (pinfunction "2_2") (pintype "passive"))
      (node (ref "R19") (pin "2") (pinfunction "2_2") (pintype "passive"))
      (node (ref "R20") (pin "2") (pinfunction "2_2") (pintype "passive"))
    )
    (net (code "95") (name "L_~{RESET}") (class "Default")
      (node (ref "C34") (pin "1") (pinfunction "1_1") (pintype "passive"))
      (node (ref "IC1") (pin "3") (pinfunction "PIO0_0/~{RESET}_3") (pintype "bidirectional"))
      (node (ref "JP1") (pin "1") (pinfunction "1_1") (pintype "passive"))
      (node (ref "R52") (pin "2") (pinfunction "2_2") (pintype "passive"))
    )
    (net (code "96") (name "Net-(C16-Pad1)") (class "Default")
      (node (ref "C16") (pin "1") (pinfunction "1_1") (pintype "passive"))
      (node (ref "R21") (pin "1") (pinfunction "1_1") (pintype "passive"))
      (node (ref "R22") (pin "1") (pinfunction "1_1") (pintype "passive"))
    )
    (net (code "97") (name "Net-(DCDC1-VIN+)") (class "Default")
      (node (ref "DCDC1") (pin "2") (pinfunction "VIN+_2") (pintype "bidirectional"))
      (node (ref "DCDC2") (pin "2") (pinfunction "VIN+_2") (pintype "bidirectional"))
      (node (ref "DCIN") (pin "3") (pinfunction "VO_3") (pintype "bidirectional"))
      (node (ref "L3") (pin "2") (pinfunction "2_2") (pintype "passive"))
      (node (ref "L4") (pin "2") (pinfunction "2_2") (pintype "passive"))
    )
    (net (code "98") (name "Net-(DCDC1-VOUT+)") (class "Default")
      (node (ref "C4") (pin "1") (pinfunction "1_1") (pintype "passive"))
      (node (ref "DCDC1") (pin "5") (pinfunction "VOUT+_5") (pintype "bidirectional"))
      (node (ref "L2") (pin "2") (pinfunction "2_2") (pintype "passive"))
    )
    (net (code "99") (name "Net-(DCDC2-VIN-)") (class "Default")
      (node (ref "C17") (pin "2") (pinfunction "2_2") (pintype "passive"))
      (node (ref "C20") (pin "2") (pinfunction "2_2") (pintype "passive"))
      (node (ref "C26") (pin "2") (pinfunction "2_2") (pintype "passive"))
      (node (ref "DCDC2") (pin "1") (pinfunction "VIN-_1") (pintype "bidirectional"))
      (node (ref "IC5") (pin "2") (pinfunction "VSS_2") (pintype "bidirectional"))
      (node (ref "IC6") (pin "4") (pinfunction "GND1_4") (pintype "bidirectional"))
      (node (ref "L6") (pin "1") (pinfunction "1_1") (pintype "passive"))
      (node (ref "R39") (pin "2") (pinfunction "2_2") (pintype "passive"))
    )
    (net (code "100") (name "Net-(DCDC2-VOUT+)") (class "Default")
      (node (ref "C29") (pin "1") (pinfunction "1_1") (pintype "passive"))
      (node (ref "DCDC2") (pin "5") (pinfunction "VOUT+_5") (pintype "bidirectional"))
      (node (ref "L12") (pin "2") (pinfunction "2_2") (pintype "passive"))
    )
    (net (code "101") (name "Net-(IC1-CANRX)") (class "Default")
      (node (ref "IC1") (pin "19") (pinfunction "CANRX_19") (pintype "bidirectional"))
      (node (ref "R7") (pin "1") (pinfunction "1_1") (pintype "passive"))
    )
    (net (code "102") (name "Net-(IC1-CANTX)") (class "Default")
      (node (ref "IC1") (pin "20") (pinfunction "CANTX_20") (pintype "bidirectional"))
      (node (ref "R6") (pin "1") (pinfunction "1_1") (pintype "passive"))
    )
    (net (code "103") (name "Net-(IC1-PIO2_0{slash}~{DTR}{slash}SSEL1)") (class "Default")
      (node (ref "IC1") (pin "2") (pinfunction "PIO2_0/~{DTR}/SSEL1_2") (pintype "bidirectional"))
      (node (ref "R1") (pin "1") (pinfunction "1_1") (pintype "passive"))
    )
    (net (code "104") (name "Net-(IC1-PIO2_1{slash}~{DSR}{slash}SCK1)") (class "Default")
      (node (ref "IC1") (pin "13") (pinfunction "PIO2_1/~{DSR}/SCK1_13") (pintype "bidirectional"))
      (node (ref "R3") (pin "1") (pinfunction "1_1") (pintype "passive"))
    )
    (net (code "105") (name "Net-(IC1-PIO2_2{slash}~{DCD}{slash}MISO1)") (class "Default")
      (node (ref "IC1") (pin "26") (pinfunction "PIO2_2/~{DCD}/MISO1_26") (pintype "bidirectional"))
      (node (ref "R4") (pin "1") (pinfunction "1_1") (pintype "passive"))
    )
    (net (code "106") (name "Net-(IC1-PIO2_3{slash}~{RI}{slash}MOSI1)") (class "Default")
      (node (ref "IC1") (pin "38") (pinfunction "PIO2_3/~{RI}/MOSI1_38") (pintype "bidirectional"))
      (node (ref "R5") (pin "1") (pinfunction "1_1") (pintype "passive"))
    )
    (net (code "107") (name "Net-(IC1-XTALIN)") (class "Default")
      (node (ref "C15") (pin "2") (pinfunction "2_2") (pintype "passive"))
      (node (ref "IC1") (pin "6") (pinfunction "XTALIN_6") (pintype "bidirectional"))
      (node (ref "Y1") (pin "2") (pinfunction "2_2") (pintype "passive"))
    )
    (net (code "108") (name "Net-(IC1-XTALOUT)") (class "Default")
      (node (ref "C14") (pin "2") (pinfunction "2_2") (pintype "passive"))
      (node (ref "IC1") (pin "7") (pinfunction "XTALOUT_7") (pintype "bidirectional"))
      (node (ref "Y1") (pin "1") (pinfunction "1_1") (pintype "passive"))
    )
    (net (code "109") (name "Net-(IC3-I2)") (class "Default")
      (node (ref "IC3") (pin "3") (pinfunction "I2_3") (pintype "bidirectional"))
      (node (ref "R14") (pin "2") (pinfunction "2_2") (pintype "passive"))
    )
    (net (code "110") (name "Net-(IC3-O1)") (class "Default")
      (node (ref "IC3") (pin "2") (pinfunction "O1_2") (pintype "bidirectional"))
      (node (ref "R13") (pin "2") (pinfunction "2_2") (pintype "passive"))
    )
    (net (code "111") (name "Net-(IC3-VDD1)") (class "Default")
      (node (ref "C18") (pin "1") (pinfunction "1_1") (pintype "passive"))
      (node (ref "C6") (pin "1") (pinfunction "1_1") (pintype "passive"))
      (node (ref "C7") (pin "1") (pinfunction "1_1") (pintype "passive"))
      (node (ref "IC3") (pin "1") (pinfunction "VDD1_1") (pintype "bidirectional"))
      (node (ref "IC4") (pin "3") (pinfunction "VDD_3") (pintype "bidirectional"))
      (node (ref "L3") (pin "1") (pinfunction "1_1") (pintype "passive"))
    )
    (net (code "112") (name "Net-(IC4-CANH)") (class "Default")
      (node (ref "IC4") (pin "7") (pinfunction "CANH_7") (pintype "bidirectional"))
      (node (ref "L8") (pin "5") (pinfunction "2_5") (pintype "passive"))
    )
    (net (code "113") (name "Net-(IC4-CANL)") (class "Default")
      (node (ref "IC4") (pin "6") (pinfunction "CANL_6") (pintype "bidirectional"))
      (node (ref "L8") (pin "4") (pinfunction "4_4") (pintype "passive"))
    )
    (net (code "114") (name "Net-(IC4-RS)") (class "Default")
      (node (ref "IC4") (pin "8") (pinfunction "RS_8") (pintype "bidirectional"))
      (node (ref "R12") (pin "1") (pinfunction "1_1") (pintype "passive"))
    )
    (net (code "115") (name "Net-(IC4-RX)") (class "Default")
      (node (ref "IC4") (pin "4") (pinfunction "RX_4") (pintype "bidirectional"))
      (node (ref "R14") (pin "1") (pinfunction "1_1") (pintype "passive"))
    )
    (net (code "116") (name "Net-(IC4-TX)") (class "Default")
      (node (ref "IC4") (pin "1") (pinfunction "TX_1") (pintype "bidirectional"))
      (node (ref "R13") (pin "1") (pinfunction "1_1") (pintype "passive"))
    )
    (net (code "117") (name "Net-(IC5-CANH)") (class "Default")
      (node (ref "IC5") (pin "7") (pinfunction "CANH_7") (pintype "bidirectional"))
      (node (ref "L11") (pin "5") (pinfunction "2_5") (pintype "passive"))
    )
    (net (code "118") (name "Net-(IC5-CANL)") (class "Default")
      (node (ref "IC5") (pin "6") (pinfunction "CANL_6") (pintype "bidirectional"))
      (node (ref "L11") (pin "4") (pinfunction "4_4") (pintype "passive"))
    )
    (net (code "119") (name "Net-(IC5-RS)") (class "Default")
      (node (ref "IC5") (pin "8") (pinfunction "RS_8") (pintype "bidirectional"))
      (node (ref "R39") (pin "1") (pinfunction "1_1") (pintype "passive"))
    )
    (net (code "120") (name "Net-(IC5-RX)") (class "Default")
      (node (ref "IC5") (pin "4") (pinfunction "RX_4") (pintype "bidirectional"))
      (node (ref "R41") (pin "1") (pinfunction "1_1") (pintype "passive"))
    )
    (net (code "121") (name "Net-(IC5-TX)") (class "Default")
      (node (ref "IC5") (pin "1") (pinfunction "TX_1") (pintype "bidirectional"))
      (node (ref "R40") (pin "1") (pinfunction "1_1") (pintype "passive"))
    )
    (net (code "122") (name "Net-(IC5-VDD)") (class "Default")
      (node (ref "C17") (pin "1") (pinfunction "1_1") (pintype "passive"))
      (node (ref "C20") (pin "1") (pinfunction "1_1") (pintype "passive"))
      (node (ref "C26") (pin "1") (pinfunction "1_1") (pintype "passive"))
      (node (ref "IC5") (pin "3") (pinfunction "VDD_3") (pintype "bidirectional"))
      (node (ref "IC6") (pin "1") (pinfunction "VDD1_1") (pintype "bidirectional"))
      (node (ref "L4") (pin "1") (pinfunction "1_1") (pintype "passive"))
    )
    (net (code "123") (name "Net-(IC6-I2)") (class "Default")
      (node (ref "IC6") (pin "3") (pinfunction "I2_3") (pintype "bidirectional"))
      (node (ref "R41") (pin "2") (pinfunction "2_2") (pintype "passive"))
    )
    (net (code "124") (name "Net-(IC6-O1)") (class "Default")
      (node (ref "IC6") (pin "2") (pinfunction "O1_2") (pintype "bidirectional"))
      (node (ref "R40") (pin "2") (pinfunction "2_2") (pintype "passive"))
    )
    (net (code "125") (name "Net-(IC7-CANRX)") (class "Default")
      (node (ref "IC7") (pin "19") (pinfunction "CANRX_19") (pintype "bidirectional"))
      (node (ref "R49") (pin "1") (pinfunction "1_1") (pintype "passive"))
    )
    (net (code "126") (name "Net-(IC7-CANTX)") (class "Default")
      (node (ref "IC7") (pin "20") (pinfunction "CANTX_20") (pintype "bidirectional"))
      (node (ref "R48") (pin "1") (pinfunction "1_1") (pintype "passive"))
    )
    (net (code "127") (name "Net-(IC7-PIO2_0{slash}~{DTR}{slash}SSEL1)") (class "Default")
      (node (ref "IC7") (pin "2") (pinfunction "PIO2_0/~{DTR}/SSEL1_2") (pintype "bidirectional"))
      (node (ref "R44") (pin "1") (pinfunction "1_1") (pintype "passive"))
    )
    (net (code "128") (name "Net-(IC7-PIO2_1{slash}~{DSR}{slash}SCK1)") (class "Default")
      (node (ref "IC7") (pin "13") (pinfunction "PIO2_1/~{DSR}/SCK1_13") (pintype "bidirectional"))
      (node (ref "R45") (pin "1") (pinfunction "1_1") (pintype "passive"))
    )
    (net (code "129") (name "Net-(IC7-PIO2_2{slash}~{DCD}{slash}MISO1)") (class "Default")
      (node (ref "IC7") (pin "26") (pinfunction "PIO2_2/~{DCD}/MISO1_26") (pintype "bidirectional"))
      (node (ref "R46") (pin "1") (pinfunction "1_1") (pintype "passive"))
    )
    (net (code "130") (name "Net-(IC7-PIO2_3{slash}~{RI}{slash}MOSI1)") (class "Default")
      (node (ref "IC7") (pin "38") (pinfunction "PIO2_3/~{RI}/MOSI1_38") (pintype "bidirectional"))
      (node (ref "R47") (pin "1") (pinfunction "1_1") (pintype "passive"))
    )
    (net (code "131") (name "Net-(IC7-XTALIN)") (class "Default")
      (node (ref "C31") (pin "2") (pinfunction "2_2") (pintype "passive"))
      (node (ref "IC7") (pin "6") (pinfunction "XTALIN_6") (pintype "bidirectional"))
      (node (ref "Y2") (pin "2") (pinfunction "2_2") (pintype "passive"))
    )
    (net (code "132") (name "Net-(IC7-XTALOUT)") (class "Default")
      (node (ref "C25") (pin "2") (pinfunction "2_2") (pintype "passive"))
      (node (ref "IC7") (pin "7") (pinfunction "XTALOUT_7") (pintype "bidirectional"))
      (node (ref "Y2") (pin "1") (pinfunction "1_1") (pintype "passive"))
    )
    (net (code "133") (name "Net-(L5-Pad2)") (class "Default")
      (node (ref "L5") (pin "2") (pinfunction "2_2") (pintype "passive"))
      (node (ref "V+R1") (pin "1") (pinfunction "1_1") (pintype "passive"))
    )
    (net (code "134") (name "Net-(L7-Pad2)") (class "Default")
      (node (ref "L7") (pin "2") (pinfunction "2_2") (pintype "passive"))
      (node (ref "V+R") (pin "1") (pinfunction "1_1") (pintype "passive"))
    )
    (net (code "135") (name "Net-(LED1-PadC)") (class "Default")
      (node (ref "LED1") (pin "C") (pinfunction "C_C") (pintype "passive"))
      (node (ref "R8") (pin "2") (pinfunction "2_2") (pintype "passive"))
    )
    (net (code "136") (name "Net-(LED2-PadC)") (class "Default")
      (node (ref "LED2") (pin "C") (pinfunction "C_C") (pintype "passive"))
      (node (ref "R53") (pin "2") (pinfunction "2_2") (pintype "passive"))
    )
    (net (code "137") (name "Net-(LED18-PadC)") (class "Default")
      (node (ref "LED18") (pin "C") (pinfunction "C_C") (pintype "passive"))
      (node (ref "R42") (pin "2") (pinfunction "2_2") (pintype "passive"))
    )
    (net (code "138") (name "Net-(LED19-PadC)") (class "Default")
      (node (ref "LED19") (pin "C") (pinfunction "C_C") (pintype "passive"))
      (node (ref "R43") (pin "2") (pinfunction "2_2") (pintype "passive"))
    )
    (net (code "139") (name "Net-(Q1-G)") (class "Default")
      (node (ref "D2") (pin "A") (pinfunction "A_A") (pintype "passive"))
      (node (ref "Q1") (pin "1") (pinfunction "G_1") (pintype "passive"))
      (node (ref "RGQ1_1") (pin "2") (pinfunction "2_2") (pintype "passive"))
      (node (ref "RGQ1_2") (pin "2") (pinfunction "2_2") (pintype "passive"))
    )
    (net (code "140") (name "Net-(Q1-S)") (class "Default")
      (node (ref "D2") (pin "C") (pinfunction "C_C") (pintype "passive"))
      (node (ref "Q1") (pin "2") (pinfunction "S_2") (pintype "passive"))
      (node (ref "RGQ1_1") (pin "1") (pinfunction "1_1") (pintype "passive"))
      (node (ref "V+R") (pin "2") (pinfunction "2_2") (pintype "passive"))
    )
    (net (code "141") (name "Net-(Q2-D)") (class "Default")
      (node (ref "Q2") (pin "3") (pinfunction "D_3") (pintype "passive"))
      (node (ref "RGQ1_2") (pin "1") (pinfunction "1_1") (pintype "passive"))
    )
    (net (code "142") (name "Net-(Q3-D)") (class "Default")
      (node (ref "Q3") (pin "3") (pinfunction "D_3") (pintype "passive"))
      (node (ref "R8") (pin "1") (pinfunction "1_1") (pintype "passive"))
    )
    (net (code "143") (name "Net-(Q4-D)") (class "Default")
      (node (ref "Q4") (pin "3") (pinfunction "D_3") (pintype "passive"))
      (node (ref "R53") (pin "1") (pinfunction "1_1") (pintype "passive"))
    )
    (net (code "144") (name "Net-(Q5-D)") (class "Default")
      (node (ref "Q5") (pin "3") (pinfunction "D_3") (pintype "passive"))
      (node (ref "RGQ1_5") (pin "1") (pinfunction "1_1") (pintype "passive"))
    )
    (net (code "145") (name "Net-(Q6-G)") (class "Default")
      (node (ref "D4") (pin "A") (pinfunction "A_A") (pintype "passive"))
      (node (ref "Q6") (pin "1") (pinfunction "G_1") (pintype "passive"))
      (node (ref "RGQ1_4") (pin "2") (pinfunction "2_2") (pintype "passive"))
      (node (ref "RGQ1_5") (pin "2") (pinfunction "2_2") (pintype "passive"))
    )
    (net (code "146") (name "Net-(Q6-S)") (class "Default")
      (node (ref "D4") (pin "C") (pinfunction "C_C") (pintype "passive"))
      (node (ref "Q6") (pin "2") (pinfunction "S_2") (pintype "passive"))
      (node (ref "RGQ1_4") (pin "1") (pinfunction "1_1") (pintype "passive"))
      (node (ref "V+R1") (pin "2") (pinfunction "2_2") (pintype "passive"))
    )
    (net (code "147") (name "Net-(QB1-D)") (class "Default")
      (node (ref "QB1") (pin "3") (pinfunction "D_3") (pintype "passive"))
      (node (ref "RP1") (pin "2") (pinfunction "2_2") (pintype "passive"))
    )
    (net (code "148") (name "Net-(QB1-G)") (class "Default")
      (node (ref "QB1") (pin "1") (pinfunction "G_1") (pintype "passive"))
      (node (ref "RBG1") (pin "1") (pinfunction "1_1") (pintype "passive"))
    )
    (net (code "149") (name "Net-(QB2-D)") (class "Default")
      (node (ref "QB2") (pin "3") (pinfunction "D_3") (pintype "passive"))
      (node (ref "RP2") (pin "2") (pinfunction "2_2") (pintype "passive"))
    )
    (net (code "150") (name "Net-(QB2-G)") (class "Default")
      (node (ref "QB2") (pin "1") (pinfunction "G_1") (pintype "passive"))
      (node (ref "RBG2") (pin "1") (pinfunction "1_1") (pintype "passive"))
    )
    (net (code "151") (name "Net-(QB3-D)") (class "Default")
      (node (ref "QB3") (pin "3") (pinfunction "D_3") (pintype "passive"))
      (node (ref "RP3") (pin "2") (pinfunction "2_2") (pintype "passive"))
    )
    (net (code "152") (name "Net-(QB3-G)") (class "Default")
      (node (ref "QB3") (pin "1") (pinfunction "G_1") (pintype "passive"))
      (node (ref "RBG3") (pin "1") (pinfunction "1_1") (pintype "passive"))
    )
    (net (code "153") (name "Net-(QB4-D)") (class "Default")
      (node (ref "QB4") (pin "3") (pinfunction "D_3") (pintype "passive"))
      (node (ref "RP4") (pin "2") (pinfunction "2_2") (pintype "passive"))
    )
    (net (code "154") (name "Net-(QB4-G)") (class "Default")
      (node (ref "QB4") (pin "1") (pinfunction "G_1") (pintype "passive"))
      (node (ref "RBG4") (pin "1") (pinfunction "1_1") (pintype "passive"))
    )
    (net (code "155") (name "Net-(QB5-D)") (class "Default")
      (node (ref "QB5") (pin "3") (pinfunction "D_3") (pintype "passive"))
      (node (ref "RP5") (pin "2") (pinfunction "2_2") (pintype "passive"))
    )
    (net (code "156") (name "Net-(QB5-G)") (class "Default")
      (node (ref "QB5") (pin "1") (pinfunction "G_1") (pintype "passive"))
      (node (ref "RBG5") (pin "1") (pinfunction "1_1") (pintype "passive"))
    )
    (net (code "157") (name "Net-(QB6-D)") (class "Default")
      (node (ref "QB6") (pin "3") (pinfunction "D_3") (pintype "passive"))
      (node (ref "RP6") (pin "2") (pinfunction "2_2") (pintype "passive"))
    )
    (net (code "158") (name "Net-(QB6-G)") (class "Default")
      (node (ref "QB6") (pin "1") (pinfunction "G_1") (pintype "passive"))
      (node (ref "RBG6") (pin "1") (pinfunction "1_1") (pintype "passive"))
    )
    (net (code "159") (name "Net-(QB7-D)") (class "Default")
      (node (ref "QB7") (pin "3") (pinfunction "D_3") (pintype "passive"))
      (node (ref "RP7") (pin "2") (pinfunction "2_2") (pintype "passive"))
    )
    (net (code "160") (name "Net-(QB7-G)") (class "Default")
      (node (ref "QB7") (pin "1") (pinfunction "G_1") (pintype "passive"))
      (node (ref "RBG7") (pin "1") (pinfunction "1_1") (pintype "passive"))
    )
    (net (code "161") (name "Net-(QB8-D)") (class "Default")
      (node (ref "QB8") (pin "3") (pinfunction "D_3") (pintype "passive"))
      (node (ref "RP8") (pin "2") (pinfunction "2_2") (pintype "passive"))
    )
    (net (code "162") (name "Net-(QB8-G)") (class "Default")
      (node (ref "QB8") (pin "1") (pinfunction "G_1") (pintype "passive"))
      (node (ref "RBG8") (pin "1") (pinfunction "1_1") (pintype "passive"))
    )
    (net (code "163") (name "Net-(QB9-D)") (class "Default")
      (node (ref "QB9") (pin "3") (pinfunction "D_3") (pintype "passive"))
      (node (ref "RP9") (pin "2") (pinfunction "2_2") (pintype "passive"))
    )
    (net (code "164") (name "Net-(QB9-G)") (class "Default")
      (node (ref "QB9") (pin "1") (pinfunction "G_1") (pintype "passive"))
      (node (ref "RBG9") (pin "1") (pinfunction "1_1") (pintype "passive"))
    )
    (net (code "165") (name "Net-(QB10-D)") (class "Default")
      (node (ref "QB10") (pin "3") (pinfunction "D_3") (pintype "passive"))
      (node (ref "RP10") (pin "2") (pinfunction "2_2") (pintype "passive"))
    )
    (net (code "166") (name "Net-(QB10-G)") (class "Default")
      (node (ref "QB10") (pin "1") (pinfunction "G_1") (pintype "passive"))
      (node (ref "RBG10") (pin "1") (pinfunction "1_1") (pintype "passive"))
    )
    (net (code "167") (name "Net-(QB11-D)") (class "Default")
      (node (ref "QB11") (pin "3") (pinfunction "D_3") (pintype "passive"))
      (node (ref "RP11") (pin "2") (pinfunction "2_2") (pintype "passive"))
    )
    (net (code "168") (name "Net-(QB11-G)") (class "Default")
      (node (ref "QB11") (pin "1") (pinfunction "G_1") (pintype "passive"))
      (node (ref "RBG11") (pin "1") (pinfunction "1_1") (pintype "passive"))
    )
    (net (code "169") (name "Net-(QB12-D)") (class "Default")
      (node (ref "QB12") (pin "3") (pinfunction "D_3") (pintype "passive"))
      (node (ref "RP12") (pin "2") (pinfunction "2_2") (pintype "passive"))
    )
    (net (code "170") (name "Net-(QB12-G)") (class "Default")
      (node (ref "QB12") (pin "1") (pinfunction "G_1") (pintype "passive"))
      (node (ref "RBG12") (pin "1") (pinfunction "1_1") (pintype "passive"))
    )
    (net (code "171") (name "Net-(QB13-D)") (class "Default")
      (node (ref "QB13") (pin "3") (pinfunction "D_3") (pintype "passive"))
      (node (ref "RP13") (pin "2") (pinfunction "2_2") (pintype "passive"))
    )
    (net (code "172") (name "Net-(QB13-G)") (class "Default")
      (node (ref "QB13") (pin "1") (pinfunction "G_1") (pintype "passive"))
      (node (ref "RBG13") (pin "1") (pinfunction "1_1") (pintype "passive"))
    )
    (net (code "173") (name "Net-(QB14-D)") (class "Default")
      (node (ref "QB14") (pin "3") (pinfunction "D_3") (pintype "passive"))
      (node (ref "RP14") (pin "2") (pinfunction "2_2") (pintype "passive"))
    )
    (net (code "174") (name "Net-(QB14-G)") (class "Default")
      (node (ref "QB14") (pin "1") (pinfunction "G_1") (pintype "passive"))
      (node (ref "RBG14") (pin "1") (pinfunction "1_1") (pintype "passive"))
    )
    (net (code "175") (name "Net-(QB15-D)") (class "Default")
      (node (ref "QB15") (pin "3") (pinfunction "D_3") (pintype "passive"))
      (node (ref "RP15") (pin "2") (pinfunction "2_2") (pintype "passive"))
    )
    (net (code "176") (name "Net-(QB15-G)") (class "Default")
      (node (ref "QB15") (pin "1") (pinfunction "G_1") (pintype "passive"))
      (node (ref "RBG15") (pin "1") (pinfunction "1_1") (pintype "passive"))
    )
    (net (code "177") (name "Net-(QB16-D)") (class "Default")
      (node (ref "QB16") (pin "3") (pinfunction "D_3") (pintype "passive"))
      (node (ref "RP16") (pin "2") (pinfunction "2_2") (pintype "passive"))
    )
    (net (code "178") (name "Net-(QB16-G)") (class "Default")
      (node (ref "QB16") (pin "1") (pinfunction "G_1") (pintype "passive"))
      (node (ref "RBG16") (pin "1") (pinfunction "1_1") (pintype "passive"))
    )
    (net (code "179") (name "Net-(R21-Pad2)") (class "Default")
      (node (ref "R21") (pin "2") (pinfunction "2_2") (pintype "passive"))
      (node (ref "SJ1") (pin "1") (pinfunction "1_1") (pintype "passive"))
    )
    (net (code "180") (name "unconnected-(IC1-PIO0_2{slash}SSEL{slash}CT16B0_CAP0-Pad10)") (class "Default")
      (node (ref "IC1") (pin "10") (pinfunction "PIO0_2/SSEL/CT16B0_CAP0_10") (pintype "bidirectional"))
    )
    (net (code "181") (name "unconnected-(IC1-PIO0_4{slash}SCL-Pad15)") (class "Default")
      (node (ref "IC1") (pin "15") (pinfunction "PIO0_4/SCL_15") (pintype "bidirectional"))
    )
    (net (code "182") (name "unconnected-(IC1-PIO0_5{slash}SDA-Pad16)") (class "Default")
      (node (ref "IC1") (pin "16") (pinfunction "PIO0_5/SDA_16") (pintype "bidirectional"))
    )
    (net (code "183") (name "unconnected-(IC1-PIO0_6{slash}SCK0-Pad22)") (class "Default")
      (node (ref "IC1") (pin "22") (pinfunction "PIO0_6/SCK0_22") (pintype "bidirectional"))
    )
    (net (code "184") (name "unconnected-(IC1-PIO0_7{slash}~{CTS}-Pad23)") (class "Default")
      (node (ref "IC1") (pin "23") (pinfunction "PIO0_7/~{CTS}_23") (pintype "bidirectional"))
    )
    (net (code "185") (name "unconnected-(IC1-PIO0_8{slash}MISO0{slash}CT16B0_MAT0-Pad27)") (class "Default")
      (node (ref "IC1") (pin "27") (pinfunction "PIO0_8/MISO0/CT16B0_MAT0_27") (pintype "bidirectional"))
    )
    (net (code "186") (name "unconnected-(IC1-PIO0_9{slash}MOSI0{slash}CT16B0_MAT1-Pad28)") (class "Default")
      (node (ref "IC1") (pin "28") (pinfunction "PIO0_9/MOSI0/CT16B0_MAT1_28") (pintype "bidirectional"))
    )
    (net (code "187") (name "unconnected-(IC1-PIO0_11{slash}AD0{slash}CT32B0_MAT3-Pad32)") (class "Default")
      (node (ref "IC1") (pin "32") (pinfunction "PIO0_11/AD0/CT32B0_MAT3_32") (pintype "bidirectional"))
    )
    (net (code "188") (name "unconnected-(IC1-PIO1_2{slash}AD3{slash}CT32B1_MAT1-Pad35)") (class "Default")
      (node (ref "IC1") (pin "35") (pinfunction "PIO1_2/AD3/CT32B1_MAT1_35") (pintype "bidirectional"))
    )
    (net (code "189") (name "unconnected-(IC1-PIO1_4{slash}AD5{slash}CT32B1_MAT3-Pad40)") (class "Default")
      (node (ref "IC1") (pin "40") (pinfunction "PIO1_4/AD5/CT32B1_MAT3_40") (pintype "bidirectional"))
    )
    (net (code "190") (name "unconnected-(IC1-PIO1_5{slash}~{RTS}{slash}CT32B0_CAP0-Pad45)") (class "Default")
      (node (ref "IC1") (pin "45") (pinfunction "PIO1_5/~{RTS}/CT32B0_CAP0_45") (pintype "bidirectional"))
    )
    (net (code "191") (name "unconnected-(IC1-PIO1_6{slash}RXD{slash}CT32B0_MAT0-Pad46)") (class "Default")
      (node (ref "IC1") (pin "46") (pinfunction "PIO1_6/RXD/CT32B0_MAT0_46") (pintype "bidirectional"))
    )
    (net (code "192") (name "unconnected-(IC1-PIO1_7{slash}TXD{slash}CT32B0_MAT1-Pad47)") (class "Default")
      (node (ref "IC1") (pin "47") (pinfunction "PIO1_7/TXD/CT32B0_MAT1_47") (pintype "bidirectional"))
    )
    (net (code "193") (name "unconnected-(IC1-PIO1_8{slash}CT16B1_CAP0-Pad9)") (class "Default")
      (node (ref "IC1") (pin "9") (pinfunction "PIO1_8/CT16B1_CAP0_9") (pintype "bidirectional"))
    )
    (net (code "194") (name "unconnected-(IC1-PIO1_9{slash}CT16B1_MAT0-Pad17)") (class "Default")
      (node (ref "IC1") (pin "17") (pinfunction "PIO1_9/CT16B1_MAT0_17") (pintype "bidirectional"))
    )
    (net (code "195") (name "unconnected-(IC1-PIO1_10{slash}AD6{slash}CT16B1_MAT1-Pad30)") (class "Default")
      (node (ref "IC1") (pin "30") (pinfunction "PIO1_10/AD6/CT16B1_MAT1_30") (pintype "bidirectional"))
    )
    (net (code "196") (name "unconnected-(IC1-PIO1_11{slash}AD7-Pad42)") (class "Default")
      (node (ref "IC1") (pin "42") (pinfunction "PIO1_11/AD7_42") (pintype "bidirectional"))
    )
    (net (code "197") (name "unconnected-(IC1-PIO2_4-Pad18)") (class "Default")
      (node (ref "IC1") (pin "18") (pinfunction "PIO2_4_18") (pintype "bidirectional"))
    )
    (net (code "198") (name "unconnected-(IC1-PIO2_5-Pad21)") (class "Default")
      (node (ref "IC1") (pin "21") (pinfunction "PIO2_5_21") (pintype "bidirectional"))
    )
    (net (code "199") (name "unconnected-(IC1-PIO2_6-Pad1)") (class "Default")
      (node (ref "IC1") (pin "1") (pinfunction "PIO2_6_1") (pintype "bidirectional"))
    )
    (net (code "200") (name "unconnected-(IC1-PIO2_7-Pad11)") (class "Default")
      (node (ref "IC1") (pin "11") (pinfunction "PIO2_7_11") (pintype "bidirectional"))
    )
    (net (code "201") (name "unconnected-(IC1-PIO2_8-Pad12)") (class "Default")
      (node (ref "IC1") (pin "12") (pinfunction "PIO2_8_12") (pintype "bidirectional"))
    )
    (net (code "202") (name "unconnected-(IC1-PIO2_9-Pad24)") (class "Default")
      (node (ref "IC1") (pin "24") (pinfunction "PIO2_9_24") (pintype "bidirectional"))
    )
    (net (code "203") (name "unconnected-(IC1-PIO2_10-Pad25)") (class "Default")
      (node (ref "IC1") (pin "25") (pinfunction "PIO2_10_25") (pintype "bidirectional"))
    )
    (net (code "204") (name "unconnected-(IC1-PIO2_11{slash}SCK0-Pad31)") (class "Default")
      (node (ref "IC1") (pin "31") (pinfunction "PIO2_11/SCK0_31") (pintype "bidirectional"))
    )
    (net (code "205") (name "unconnected-(IC1-PIO3_0{slash}~{DTR}-Pad36)") (class "Default")
      (node (ref "IC1") (pin "36") (pinfunction "PIO3_0/~{DTR}_36") (pintype "bidirectional"))
    )
    (net (code "206") (name "unconnected-(IC1-PIO3_1{slash}~{DSR}-Pad37)") (class "Default")
      (node (ref "IC1") (pin "37") (pinfunction "PIO3_1/~{DSR}_37") (pintype "bidirectional"))
    )
    (net (code "207") (name "unconnected-(IC1-PIO3_2{slash}~{DCD}-Pad43)") (class "Default")
      (node (ref "IC1") (pin "43") (pinfunction "PIO3_2/~{DCD}_43") (pintype "bidirectional"))
    )
    (net (code "208") (name "unconnected-(IC2-S9-Pad9)") (class "Default")
      (node (ref "IC2") (pin "9") (pinfunction "S9_9") (pintype "bidirectional"))
    )
    (net (code "209") (name "unconnected-(IC2-S10-Pad7)") (class "Default")
      (node (ref "IC2") (pin "7") (pinfunction "S10_7") (pintype "bidirectional"))
    )
    (net (code "210") (name "unconnected-(IC2-S11-Pad5)") (class "Default")
      (node (ref "IC2") (pin "5") (pinfunction "S11_5") (pintype "bidirectional"))
    )
    (net (code "211") (name "unconnected-(IC2-S12-Pad3)") (class "Default")
      (node (ref "IC2") (pin "3") (pinfunction "S12_3") (pintype "bidirectional"))
    )
    (net (code "212") (name "unconnected-(IC4-VRF-Pad5)") (class "Default")
      (node (ref "IC4") (pin "5") (pinfunction "VRF_5") (pintype "bidirectional"))
    )
    (net (code "213") (name "unconnected-(IC5-VRF-Pad5)") (class "Default")
      (node (ref "IC5") (pin "5") (pinfunction "VRF_5") (pintype "bidirectional"))
    )
    (net (code "214") (name "unconnected-(IC7-PIO0_2{slash}SSEL{slash}CT16B0_CAP0-Pad10)") (class "Default")
      (node (ref "IC7") (pin "10") (pinfunction "PIO0_2/SSEL/CT16B0_CAP0_10") (pintype "bidirectional"))
    )
    (net (code "215") (name "unconnected-(IC7-PIO0_4{slash}SCL-Pad15)") (class "Default")
      (node (ref "IC7") (pin "15") (pinfunction "PIO0_4/SCL_15") (pintype "bidirectional"))
    )
    (net (code "216") (name "unconnected-(IC7-PIO0_5{slash}SDA-Pad16)") (class "Default")
      (node (ref "IC7") (pin "16") (pinfunction "PIO0_5/SDA_16") (pintype "bidirectional"))
    )
    (net (code "217") (name "unconnected-(IC7-PIO0_6{slash}SCK0-Pad22)") (class "Default")
      (node (ref "IC7") (pin "22") (pinfunction "PIO0_6/SCK0_22") (pintype "bidirectional"))
    )
    (net (code "218") (name "unconnected-(IC7-PIO0_7{slash}~{CTS}-Pad23)") (class "Default")
      (node (ref "IC7") (pin "23") (pinfunction "PIO0_7/~{CTS}_23") (pintype "bidirectional"))
    )
    (net (code "219") (name "unconnected-(IC7-PIO0_8{slash}MISO0{slash}CT16B0_MAT0-Pad27)") (class "Default")
      (node (ref "IC7") (pin "27") (pinfunction "PIO0_8/MISO0/CT16B0_MAT0_27") (pintype "bidirectional"))
    )
    (net (code "220") (name "unconnected-(IC7-PIO0_9{slash}MOSI0{slash}CT16B0_MAT1-Pad28)") (class "Default")
      (node (ref "IC7") (pin "28") (pinfunction "PIO0_9/MOSI0/CT16B0_MAT1_28") (pintype "bidirectional"))
    )
    (net (code "221") (name "unconnected-(IC7-PIO0_11{slash}AD0{slash}CT32B0_MAT3-Pad32)") (class "Default")
      (node (ref "IC7") (pin "32") (pinfunction "PIO0_11/AD0/CT32B0_MAT3_32") (pintype "bidirectional"))
    )
    (net (code "222") (name "unconnected-(IC7-PIO1_2{slash}AD3{slash}CT32B1_MAT1-Pad35)") (class "Default")
      (node (ref "IC7") (pin "35") (pinfunction "PIO1_2/AD3/CT32B1_MAT1_35") (pintype "bidirectional"))
    )
    (net (code "223") (name "unconnected-(IC7-PIO1_4{slash}AD5{slash}CT32B1_MAT3-Pad40)") (class "Default")
      (node (ref "IC7") (pin "40") (pinfunction "PIO1_4/AD5/CT32B1_MAT3_40") (pintype "bidirectional"))
    )
    (net (code "224") (name "unconnected-(IC7-PIO1_5{slash}~{RTS}{slash}CT32B0_CAP0-Pad45)") (class "Default")
      (node (ref "IC7") (pin "45") (pinfunction "PIO1_5/~{RTS}/CT32B0_CAP0_45") (pintype "bidirectional"))
    )
    (net (code "225") (name "unconnected-(IC7-PIO1_6{slash}RXD{slash}CT32B0_MAT0-Pad46)") (class "Default")
      (node (ref "IC7") (pin "46") (pinfunction "PIO1_6/RXD/CT32B0_MAT0_46") (pintype "bidirectional"))
    )
    (net (code "226") (name "unconnected-(IC7-PIO1_7{slash}TXD{slash}CT32B0_MAT1-Pad47)") (class "Default")
      (node (ref "IC7") (pin "47") (pinfunction "PIO1_7/TXD/CT32B0_MAT1_47") (pintype "bidirectional"))
    )
    (net (code "227") (name "unconnected-(IC7-PIO1_8{slash}CT16B1_CAP0-Pad9)") (class "Default")
      (node (ref "IC7") (pin "9") (pinfunction "PIO1_8/CT16B1_CAP0_9") (pintype "bidirectional"))
    )
    (net (code "228") (name "unconnected-(IC7-PIO1_9{slash}CT16B1_MAT0-Pad17)") (class "Default")
      (node (ref "IC7") (pin "17") (pinfunction "PIO1_9/CT16B1_MAT0_17") (pintype "bidirectional"))
    )
    (net (code "229") (name "unconnected-(IC7-PIO1_10{slash}AD6{slash}CT16B1_MAT1-Pad30)") (class "Default")
      (node (ref "IC7") (pin "30") (pinfunction "PIO1_10/AD6/CT16B1_MAT1_30") (pintype "bidirectional"))
    )
    (net (code "230") (name "unconnected-(IC7-PIO1_11{slash}AD7-Pad42)") (class "Default")
      (node (ref "IC7") (pin "42") (pinfunction "PIO1_11/AD7_42") (pintype "bidirectional"))
    )
    (net (code "231") (name "unconnected-(IC7-PIO2_4-Pad18)") (class "Default")
      (node (ref "IC7") (pin "18") (pinfunction "PIO2_4_18") (pintype "bidirectional"))
    )
    (net (code "232") (name "unconnected-(IC7-PIO2_5-Pad21)") (class "Default")
      (node (ref "IC7") (pin "21") (pinfunction "PIO2_5_21") (pintype "bidirectional"))
    )
    (net (code "233") (name "unconnected-(IC7-PIO2_6-Pad1)") (class "Default")
      (node (ref "IC7") (pin "1") (pinfunction "PIO2_6_1") (pintype "bidirectional"))
    )
    (net (code "234") (name "unconnected-(IC7-PIO2_7-Pad11)") (class "Default")
      (node (ref "IC7") (pin "11") (pinfunction "PIO2_7_11") (pintype "bidirectional"))
    )
    (net (code "235") (name "unconnected-(IC7-PIO2_8-Pad12)") (class "Default")
      (node (ref "IC7") (pin "12") (pinfunction "PIO2_8_12") (pintype "bidirectional"))
    )
    (net (code "236") (name "unconnected-(IC7-PIO2_9-Pad24)") (class "Default")
      (node (ref "IC7") (pin "24") (pinfunction "PIO2_9_24") (pintype "bidirectional"))
    )
    (net (code "237") (name "unconnected-(IC7-PIO2_10-Pad25)") (class "Default")
      (node (ref "IC7") (pin "25") (pinfunction "PIO2_10_25") (pintype "bidirectional"))
    )
    (net (code "238") (name "unconnected-(IC7-PIO2_11{slash}SCK0-Pad31)") (class "Default")
      (node (ref "IC7") (pin "31") (pinfunction "PIO2_11/SCK0_31") (pintype "bidirectional"))
    )
    (net (code "239") (name "unconnected-(IC7-PIO3_0{slash}~{DTR}-Pad36)") (class "Default")
      (node (ref "IC7") (pin "36") (pinfunction "PIO3_0/~{DTR}_36") (pintype "bidirectional"))
    )
    (net (code "240") (name "unconnected-(IC7-PIO3_1{slash}~{DSR}-Pad37)") (class "Default")
      (node (ref "IC7") (pin "37") (pinfunction "PIO3_1/~{DSR}_37") (pintype "bidirectional"))
    )
    (net (code "241") (name "unconnected-(IC7-PIO3_2{slash}~{DCD}-Pad43)") (class "Default")
      (node (ref "IC7") (pin "43") (pinfunction "PIO3_2/~{DCD}_43") (pintype "bidirectional"))
    )
    (net (code "242") (name "unconnected-(IC8-S9-Pad9)") (class "Default")
      (node (ref "IC8") (pin "9") (pinfunction "S9_9") (pintype "bidirectional"))
    )
    (net (code "243") (name "unconnected-(IC8-S10-Pad7)") (class "Default")
      (node (ref "IC8") (pin "7") (pinfunction "S10_7") (pintype "bidirectional"))
    )
    (net (code "244") (name "unconnected-(IC8-S11-Pad5)") (class "Default")
      (node (ref "IC8") (pin "5") (pinfunction "S11_5") (pintype "bidirectional"))
    )
    (net (code "245") (name "unconnected-(IC8-S12-Pad3)") (class "Default")
      (node (ref "IC8") (pin "3") (pinfunction "S12_3") (pintype "bidirectional"))
    )
  )
)
